# VALVEBOARD_ValveDrive3.net
KiCad netlist of a schematic drawn in Altium Designer
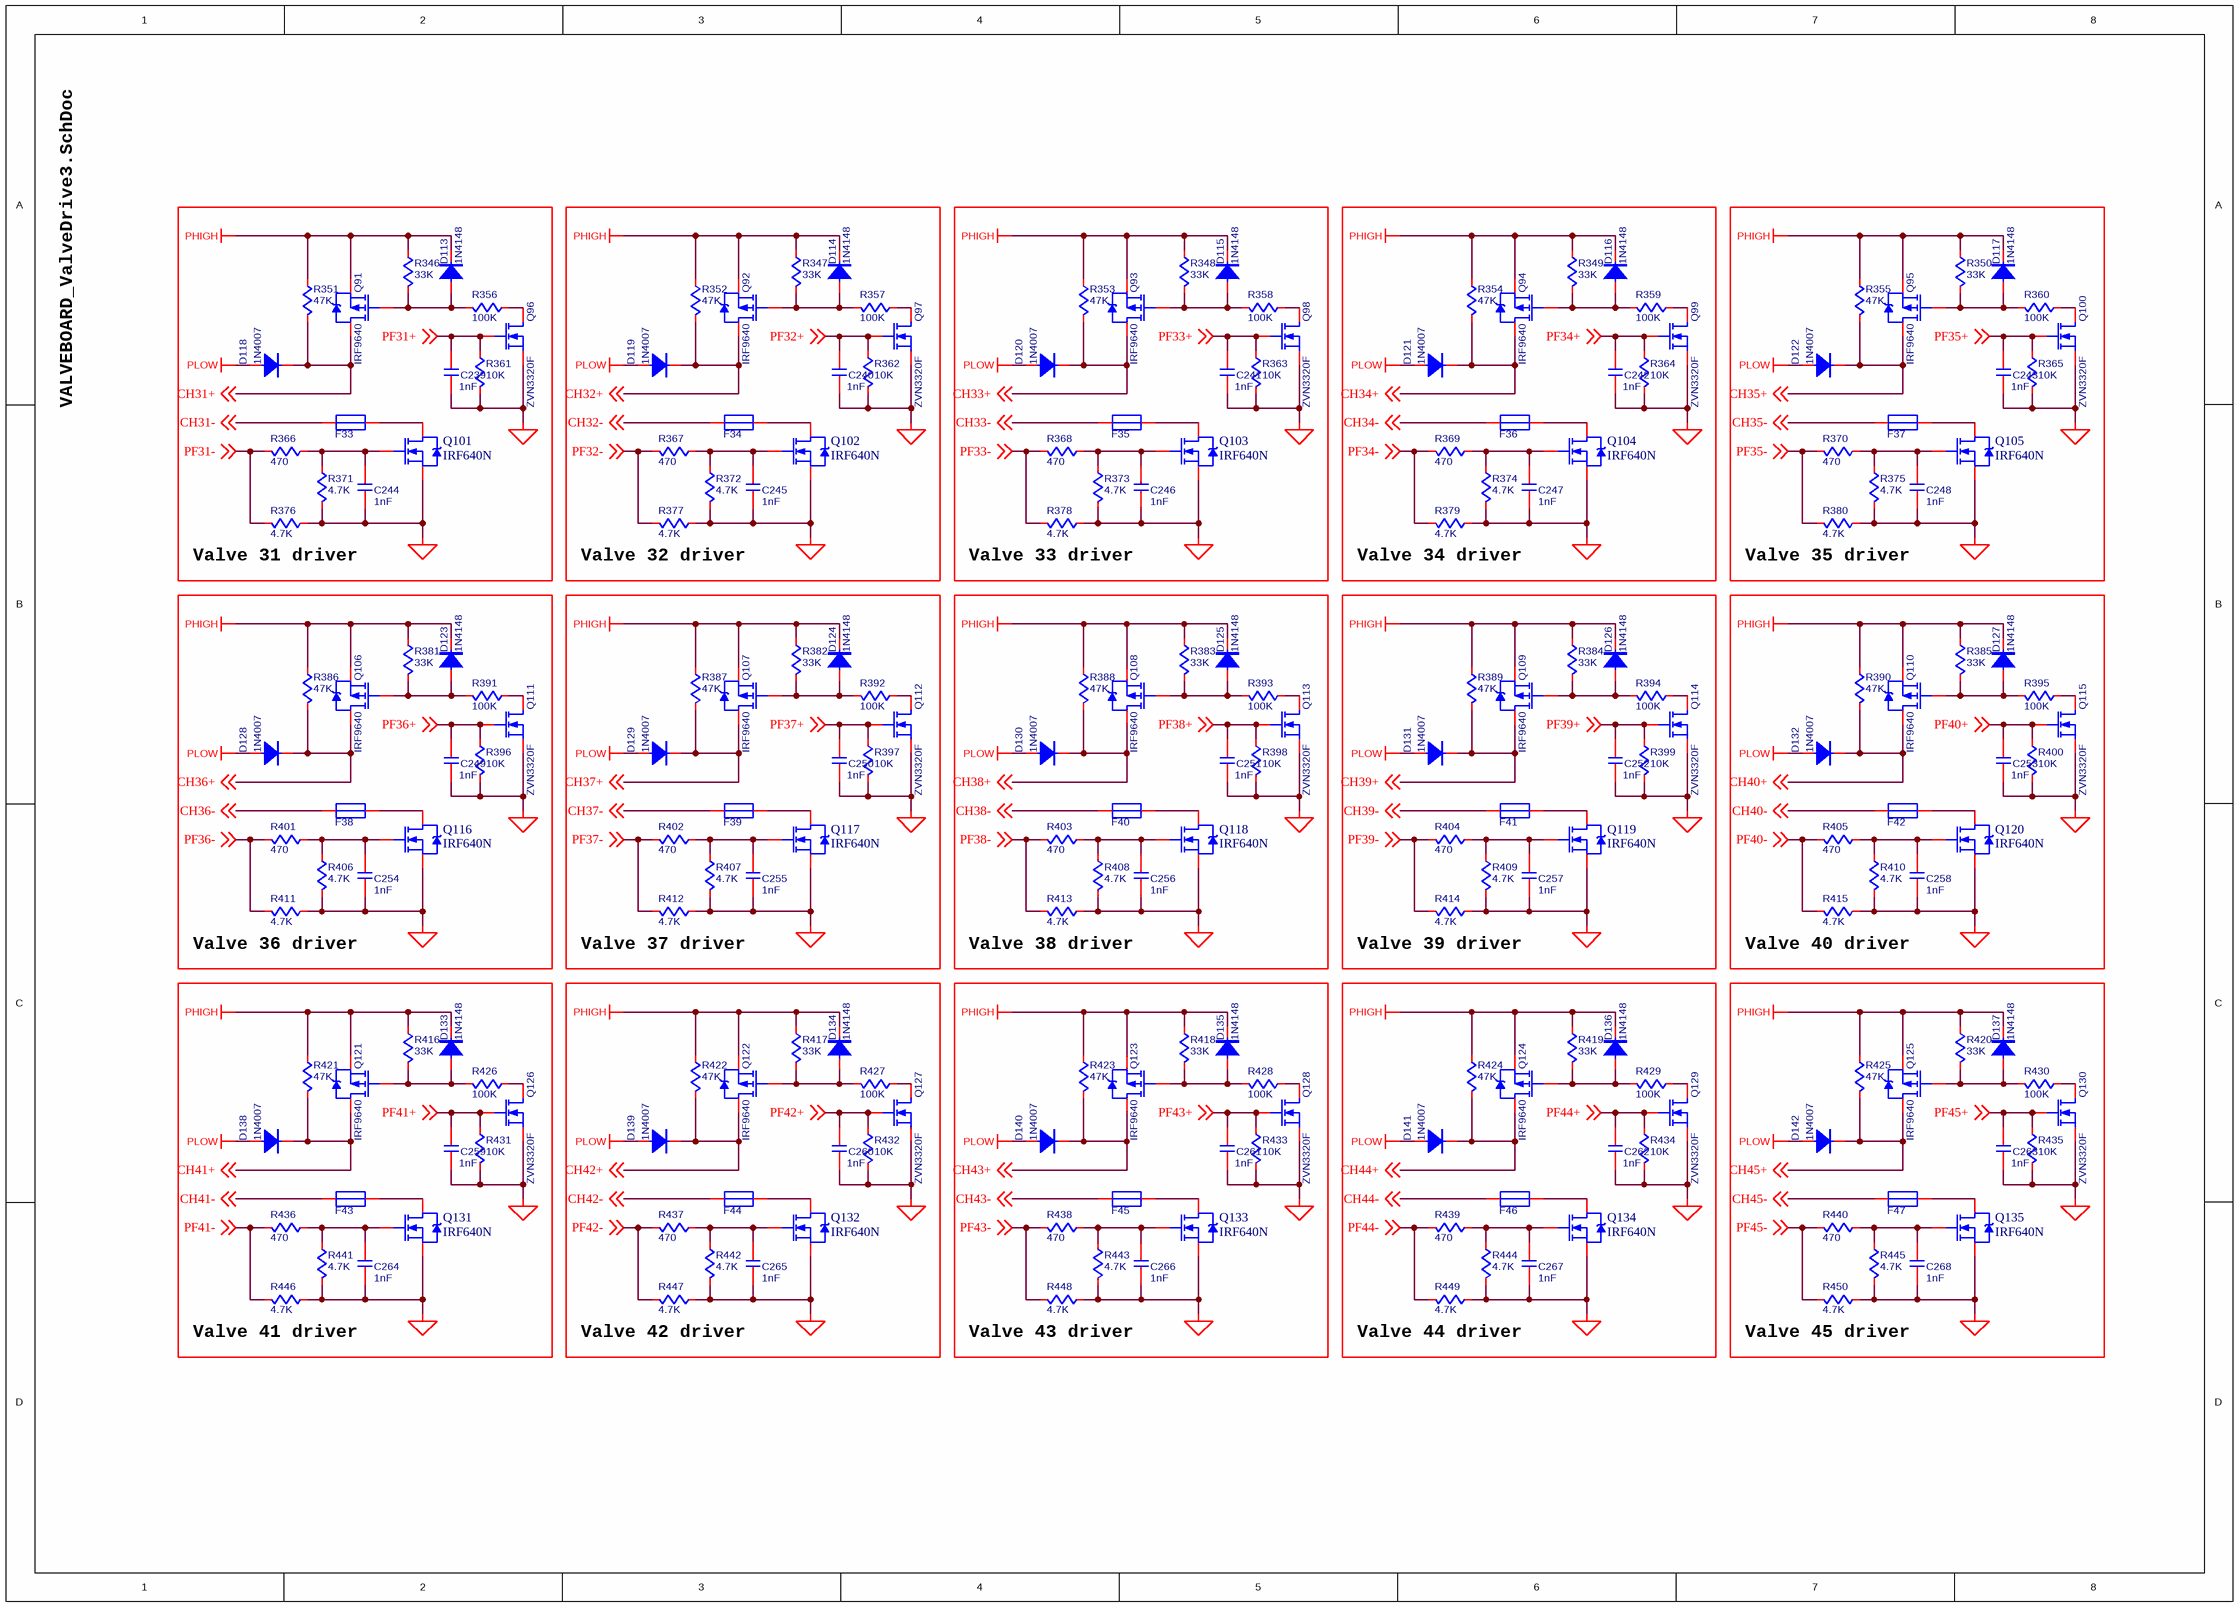
[diagram p0: VALVEBOARD_ValveDrive3.SchDoc]

(export (version "E")
  (design (tool "Eeschema 10.0.6"))
  (components
    (comp (ref "C239")
      (value "1nF")
      (footprint "zynq:C0603")
      (fields (field (name "VOLTAGE") "25V") (field (name "Comment") "C-NOMO"))
      (libsource (lib "zynq") (part "C-NOMO"))
    )
    (comp (ref "C240")
      (value "1nF")
      (footprint "zynq:C0603")
      (fields (field (name "VOLTAGE") "25V") (field (name "Comment") "C-NOMO"))
      (libsource (lib "zynq") (part "C-NOMO"))
    )
    (comp (ref "C241")
      (value "1nF")
      (footprint "zynq:C0603")
      (fields (field (name "VOLTAGE") "25V") (field (name "Comment") "C-NOMO"))
      (libsource (lib "zynq") (part "C-NOMO"))
    )
    (comp (ref "C242")
      (value "1nF")
      (footprint "zynq:C0603")
      (fields (field (name "VOLTAGE") "25V") (field (name "Comment") "C-NOMO"))
      (libsource (lib "zynq") (part "C-NOMO"))
    )
    (comp (ref "C243")
      (value "1nF")
      (footprint "zynq:C0603")
      (fields (field (name "VOLTAGE") "25V") (field (name "Comment") "C-NOMO"))
      (libsource (lib "zynq") (part "C-NOMO"))
    )
    (comp (ref "C244")
      (value "1nF")
      (footprint "zynq:C0603")
      (fields (field (name "VOLTAGE") "25V") (field (name "Comment") "C-NOMO"))
      (libsource (lib "zynq") (part "C-NOMO"))
    )
    (comp (ref "C245")
      (value "1nF")
      (footprint "zynq:C0603")
      (fields (field (name "VOLTAGE") "25V") (field (name "Comment") "C-NOMO"))
      (libsource (lib "zynq") (part "C-NOMO"))
    )
    (comp (ref "C246")
      (value "1nF")
      (footprint "zynq:C0603")
      (fields (field (name "VOLTAGE") "25V") (field (name "Comment") "C-NOMO"))
      (libsource (lib "zynq") (part "C-NOMO"))
    )
    (comp (ref "C247")
      (value "1nF")
      (footprint "zynq:C0603")
      (fields (field (name "VOLTAGE") "25V") (field (name "Comment") "C-NOMO"))
      (libsource (lib "zynq") (part "C-NOMO"))
    )
    (comp (ref "C248")
      (value "1nF")
      (footprint "zynq:C0603")
      (fields (field (name "VOLTAGE") "25V") (field (name "Comment") "C-NOMO"))
      (libsource (lib "zynq") (part "C-NOMO"))
    )
    (comp (ref "C249")
      (value "1nF")
      (footprint "zynq:C0603")
      (fields (field (name "VOLTAGE") "25V") (field (name "Comment") "C-NOMO"))
      (libsource (lib "zynq") (part "C-NOMO"))
    )
    (comp (ref "C250")
      (value "1nF")
      (footprint "zynq:C0603")
      (fields (field (name "VOLTAGE") "25V") (field (name "Comment") "C-NOMO"))
      (libsource (lib "zynq") (part "C-NOMO"))
    )
    (comp (ref "C251")
      (value "1nF")
      (footprint "zynq:C0603")
      (fields (field (name "VOLTAGE") "25V") (field (name "Comment") "C-NOMO"))
      (libsource (lib "zynq") (part "C-NOMO"))
    )
    (comp (ref "C252")
      (value "1nF")
      (footprint "zynq:C0603")
      (fields (field (name "VOLTAGE") "25V") (field (name "Comment") "C-NOMO"))
      (libsource (lib "zynq") (part "C-NOMO"))
    )
    (comp (ref "C253")
      (value "1nF")
      (footprint "zynq:C0603")
      (fields (field (name "VOLTAGE") "25V") (field (name "Comment") "C-NOMO"))
      (libsource (lib "zynq") (part "C-NOMO"))
    )
    (comp (ref "C254")
      (value "1nF")
      (footprint "zynq:C0603")
      (fields (field (name "VOLTAGE") "25V") (field (name "Comment") "C-NOMO"))
      (libsource (lib "zynq") (part "C-NOMO"))
    )
    (comp (ref "C255")
      (value "1nF")
      (footprint "zynq:C0603")
      (fields (field (name "VOLTAGE") "25V") (field (name "Comment") "C-NOMO"))
      (libsource (lib "zynq") (part "C-NOMO"))
    )
    (comp (ref "C256")
      (value "1nF")
      (footprint "zynq:C0603")
      (fields (field (name "VOLTAGE") "25V") (field (name "Comment") "C-NOMO"))
      (libsource (lib "zynq") (part "C-NOMO"))
    )
    (comp (ref "C257")
      (value "1nF")
      (footprint "zynq:C0603")
      (fields (field (name "VOLTAGE") "25V") (field (name "Comment") "C-NOMO"))
      (libsource (lib "zynq") (part "C-NOMO"))
    )
    (comp (ref "C258")
      (value "1nF")
      (footprint "zynq:C0603")
      (fields (field (name "VOLTAGE") "25V") (field (name "Comment") "C-NOMO"))
      (libsource (lib "zynq") (part "C-NOMO"))
    )
    (comp (ref "C259")
      (value "1nF")
      (footprint "zynq:C0603")
      (fields (field (name "VOLTAGE") "25V") (field (name "Comment") "C-NOMO"))
      (libsource (lib "zynq") (part "C-NOMO"))
    )
    (comp (ref "C260")
      (value "1nF")
      (footprint "zynq:C0603")
      (fields (field (name "VOLTAGE") "25V") (field (name "Comment") "C-NOMO"))
      (libsource (lib "zynq") (part "C-NOMO"))
    )
    (comp (ref "C261")
      (value "1nF")
      (footprint "zynq:C0603")
      (fields (field (name "VOLTAGE") "25V") (field (name "Comment") "C-NOMO"))
      (libsource (lib "zynq") (part "C-NOMO"))
    )
    (comp (ref "C262")
      (value "1nF")
      (footprint "zynq:C0603")
      (fields (field (name "VOLTAGE") "25V") (field (name "Comment") "C-NOMO"))
      (libsource (lib "zynq") (part "C-NOMO"))
    )
    (comp (ref "C263")
      (value "1nF")
      (footprint "zynq:C0603")
      (fields (field (name "VOLTAGE") "25V") (field (name "Comment") "C-NOMO"))
      (libsource (lib "zynq") (part "C-NOMO"))
    )
    (comp (ref "C264")
      (value "1nF")
      (footprint "zynq:C0603")
      (fields (field (name "VOLTAGE") "25V") (field (name "Comment") "C-NOMO"))
      (libsource (lib "zynq") (part "C-NOMO"))
    )
    (comp (ref "C265")
      (value "1nF")
      (footprint "zynq:C0603")
      (fields (field (name "VOLTAGE") "25V") (field (name "Comment") "C-NOMO"))
      (libsource (lib "zynq") (part "C-NOMO"))
    )
    (comp (ref "C266")
      (value "1nF")
      (footprint "zynq:C0603")
      (fields (field (name "VOLTAGE") "25V") (field (name "Comment") "C-NOMO"))
      (libsource (lib "zynq") (part "C-NOMO"))
    )
    (comp (ref "C267")
      (value "1nF")
      (footprint "zynq:C0603")
      (fields (field (name "VOLTAGE") "25V") (field (name "Comment") "C-NOMO"))
      (libsource (lib "zynq") (part "C-NOMO"))
    )
    (comp (ref "C268")
      (value "1nF")
      (footprint "zynq:C0603")
      (fields (field (name "VOLTAGE") "25V") (field (name "Comment") "C-NOMO"))
      (libsource (lib "zynq") (part "C-NOMO"))
    )
    (comp (ref "D113") (value "1N4148") (footprint "SOD-123") (libsource (lib "") (part "DIOD1_1")))
    (comp (ref "D114") (value "1N4148") (footprint "SOD-123") (libsource (lib "") (part "DIOD1_1")))
    (comp (ref "D115") (value "1N4148") (footprint "SOD-123") (libsource (lib "") (part "DIOD1_1")))
    (comp (ref "D116") (value "1N4148") (footprint "SOD-123") (libsource (lib "") (part "DIOD1_1")))
    (comp (ref "D117") (value "1N4148") (footprint "SOD-123") (libsource (lib "") (part "DIOD1_1")))
    (comp (ref "D118") (value "1N4007") (footprint "zynq:1N4148") (libsource (lib "zynq") (part "DIOD1")))
    (comp (ref "D119") (value "1N4007") (footprint "zynq:1N4148") (libsource (lib "zynq") (part "DIOD1")))
    (comp (ref "D120") (value "1N4007") (footprint "zynq:1N4148") (libsource (lib "zynq") (part "DIOD1")))
    (comp (ref "D121") (value "1N4007") (footprint "zynq:1N4148") (libsource (lib "zynq") (part "DIOD1")))
    (comp (ref "D122") (value "1N4007") (footprint "zynq:1N4148") (libsource (lib "zynq") (part "DIOD1")))
    (comp (ref "D123") (value "1N4148") (footprint "SOD-123") (libsource (lib "") (part "DIOD1_1")))
    (comp (ref "D124") (value "1N4148") (footprint "SOD-123") (libsource (lib "") (part "DIOD1_1")))
    (comp (ref "D125") (value "1N4148") (footprint "SOD-123") (libsource (lib "") (part "DIOD1_1")))
    (comp (ref "D126") (value "1N4148") (footprint "SOD-123") (libsource (lib "") (part "DIOD1_1")))
    (comp (ref "D127") (value "1N4148") (footprint "SOD-123") (libsource (lib "") (part "DIOD1_1")))
    (comp (ref "D128") (value "1N4007") (footprint "zynq:1N4148") (libsource (lib "zynq") (part "DIOD1")))
    (comp (ref "D129") (value "1N4007") (footprint "zynq:1N4148") (libsource (lib "zynq") (part "DIOD1")))
    (comp (ref "D130") (value "1N4007") (footprint "zynq:1N4148") (libsource (lib "zynq") (part "DIOD1")))
    (comp (ref "D131") (value "1N4007") (footprint "zynq:1N4148") (libsource (lib "zynq") (part "DIOD1")))
    (comp (ref "D132") (value "1N4007") (footprint "zynq:1N4148") (libsource (lib "zynq") (part "DIOD1")))
    (comp (ref "D133") (value "1N4148") (footprint "SOD-123") (libsource (lib "") (part "DIOD1_1")))
    (comp (ref "D134") (value "1N4148") (footprint "SOD-123") (libsource (lib "") (part "DIOD1_1")))
    (comp (ref "D135") (value "1N4148") (footprint "SOD-123") (libsource (lib "") (part "DIOD1_1")))
    (comp (ref "D136") (value "1N4148") (footprint "SOD-123") (libsource (lib "") (part "DIOD1_1")))
    (comp (ref "D137") (value "1N4148") (footprint "SOD-123") (libsource (lib "") (part "DIOD1_1")))
    (comp (ref "D138") (value "1N4007") (footprint "zynq:1N4148") (libsource (lib "zynq") (part "DIOD1")))
    (comp (ref "D139") (value "1N4007") (footprint "zynq:1N4148") (libsource (lib "zynq") (part "DIOD1")))
    (comp (ref "D140") (value "1N4007") (footprint "zynq:1N4148") (libsource (lib "zynq") (part "DIOD1")))
    (comp (ref "D141") (value "1N4007") (footprint "zynq:1N4148") (libsource (lib "zynq") (part "DIOD1")))
    (comp (ref "D142") (value "1N4007") (footprint "zynq:1N4148") (libsource (lib "zynq") (part "DIOD1")))
    (comp (ref "F33") (value "F50") (footprint "zynq:F-TH") (libsource (lib "zynq") (part "F50")))
    (comp (ref "F34") (value "F50") (footprint "zynq:F-TH") (libsource (lib "zynq") (part "F50")))
    (comp (ref "F35") (value "F50") (footprint "zynq:F-TH") (libsource (lib "zynq") (part "F50")))
    (comp (ref "F36") (value "F50") (footprint "zynq:F-TH") (libsource (lib "zynq") (part "F50")))
    (comp (ref "F37") (value "F50") (footprint "zynq:F-TH") (libsource (lib "zynq") (part "F50")))
    (comp (ref "F38") (value "F50") (footprint "zynq:F-TH") (libsource (lib "zynq") (part "F50")))
    (comp (ref "F39") (value "F50") (footprint "zynq:F-TH") (libsource (lib "zynq") (part "F50")))
    (comp (ref "F40") (value "F50") (footprint "zynq:F-TH") (libsource (lib "zynq") (part "F50")))
    (comp (ref "F41") (value "F50") (footprint "zynq:F-TH") (libsource (lib "zynq") (part "F50")))
    (comp (ref "F42") (value "F50") (footprint "zynq:F-TH") (libsource (lib "zynq") (part "F50")))
    (comp (ref "F43") (value "F50") (footprint "zynq:F-TH") (libsource (lib "zynq") (part "F50")))
    (comp (ref "F44") (value "F50") (footprint "zynq:F-TH") (libsource (lib "zynq") (part "F50")))
    (comp (ref "F45") (value "F50") (footprint "zynq:F-TH") (libsource (lib "zynq") (part "F50")))
    (comp (ref "F46") (value "F50") (footprint "zynq:F-TH") (libsource (lib "zynq") (part "F50")))
    (comp (ref "F47") (value "F50") (footprint "zynq:F-TH") (libsource (lib "zynq") (part "F50")))
    (comp (ref "Q91")
      (value "IRF9640")
      (footprint "TO-220AB")
      (description "P-Channel Power MOSFET")
      (fields (field (name "PUBLISHER") "Altium Limited"))
      (libsource (lib "zynq") (part "IRF9640"))
    )
    (comp (ref "Q92")
      (value "IRF9640")
      (footprint "TO-220AB")
      (description "P-Channel Power MOSFET")
      (fields (field (name "PUBLISHER") "Altium Limited"))
      (libsource (lib "zynq") (part "IRF9640"))
    )
    (comp (ref "Q93")
      (value "IRF9640")
      (footprint "TO-220AB")
      (description "P-Channel Power MOSFET")
      (fields (field (name "PUBLISHER") "Altium Limited"))
      (libsource (lib "zynq") (part "IRF9640"))
    )
    (comp (ref "Q94")
      (value "IRF9640")
      (footprint "TO-220AB")
      (description "P-Channel Power MOSFET")
      (fields (field (name "PUBLISHER") "Altium Limited"))
      (libsource (lib "zynq") (part "IRF9640"))
    )
    (comp (ref "Q95")
      (value "IRF9640")
      (footprint "TO-220AB")
      (description "P-Channel Power MOSFET")
      (fields (field (name "PUBLISHER") "Altium Limited"))
      (libsource (lib "zynq") (part "IRF9640"))
    )
    (comp (ref "Q96")
      (value "ZVN3320F")
      (footprint "zynq:ZVN3320F")
      (description "N-Channel MOSFET")
      (fields (field (name "PUBLISHER") "Altium Limited"))
      (libsource (lib "zynq") (part "ZVN3320F"))
    )
    (comp (ref "Q97")
      (value "ZVN3320F")
      (footprint "zynq:ZVN3320F")
      (description "N-Channel MOSFET")
      (fields (field (name "PUBLISHER") "Altium Limited"))
      (libsource (lib "zynq") (part "ZVN3320F"))
    )
    (comp (ref "Q98")
      (value "ZVN3320F")
      (footprint "zynq:ZVN3320F")
      (description "N-Channel MOSFET")
      (fields (field (name "PUBLISHER") "Altium Limited"))
      (libsource (lib "zynq") (part "ZVN3320F"))
    )
    (comp (ref "Q99")
      (value "ZVN3320F")
      (footprint "zynq:ZVN3320F")
      (description "N-Channel MOSFET")
      (fields (field (name "PUBLISHER") "Altium Limited"))
      (libsource (lib "zynq") (part "ZVN3320F"))
    )
    (comp (ref "Q100")
      (value "ZVN3320F")
      (footprint "zynq:ZVN3320F")
      (description "N-Channel MOSFET")
      (fields (field (name "PUBLISHER") "Altium Limited"))
      (libsource (lib "zynq") (part "ZVN3320F"))
    )
    (comp (ref "Q101")
      (value "IRF640N")
      (footprint "zynq:TO-220AB")
      (description "N-Channel Power MOSFET")
      (fields (field (name "PUBLISHER") "Altium Limited"))
      (libsource (lib "zynq") (part "IRF640N"))
    )
    (comp (ref "Q102")
      (value "IRF640N")
      (footprint "zynq:TO-220AB")
      (description "N-Channel Power MOSFET")
      (fields (field (name "PUBLISHER") "Altium Limited"))
      (libsource (lib "zynq") (part "IRF640N"))
    )
    (comp (ref "Q103")
      (value "IRF640N")
      (footprint "zynq:TO-220AB")
      (description "N-Channel Power MOSFET")
      (fields (field (name "PUBLISHER") "Altium Limited"))
      (libsource (lib "zynq") (part "IRF640N"))
    )
    (comp (ref "Q104")
      (value "IRF640N")
      (footprint "zynq:TO-220AB")
      (description "N-Channel Power MOSFET")
      (fields (field (name "PUBLISHER") "Altium Limited"))
      (libsource (lib "zynq") (part "IRF640N"))
    )
    (comp (ref "Q105")
      (value "IRF640N")
      (footprint "zynq:TO-220AB")
      (description "N-Channel Power MOSFET")
      (fields (field (name "PUBLISHER") "Altium Limited"))
      (libsource (lib "zynq") (part "IRF640N"))
    )
    (comp (ref "Q106")
      (value "IRF9640")
      (footprint "TO-220AB")
      (description "P-Channel Power MOSFET")
      (fields (field (name "PUBLISHER") "Altium Limited"))
      (libsource (lib "zynq") (part "IRF9640"))
    )
    (comp (ref "Q107")
      (value "IRF9640")
      (footprint "TO-220AB")
      (description "P-Channel Power MOSFET")
      (fields (field (name "PUBLISHER") "Altium Limited"))
      (libsource (lib "zynq") (part "IRF9640"))
    )
    (comp (ref "Q108")
      (value "IRF9640")
      (footprint "TO-220AB")
      (description "P-Channel Power MOSFET")
      (fields (field (name "PUBLISHER") "Altium Limited"))
      (libsource (lib "zynq") (part "IRF9640"))
    )
    (comp (ref "Q109")
      (value "IRF9640")
      (footprint "TO-220AB")
      (description "P-Channel Power MOSFET")
      (fields (field (name "PUBLISHER") "Altium Limited"))
      (libsource (lib "zynq") (part "IRF9640"))
    )
    (comp (ref "Q110")
      (value "IRF9640")
      (footprint "TO-220AB")
      (description "P-Channel Power MOSFET")
      (fields (field (name "PUBLISHER") "Altium Limited"))
      (libsource (lib "zynq") (part "IRF9640"))
    )
    (comp (ref "Q111")
      (value "ZVN3320F")
      (footprint "zynq:ZVN3320F")
      (description "N-Channel MOSFET")
      (fields (field (name "PUBLISHER") "Altium Limited"))
      (libsource (lib "zynq") (part "ZVN3320F"))
    )
    (comp (ref "Q112")
      (value "ZVN3320F")
      (footprint "zynq:ZVN3320F")
      (description "N-Channel MOSFET")
      (fields (field (name "PUBLISHER") "Altium Limited"))
      (libsource (lib "zynq") (part "ZVN3320F"))
    )
    (comp (ref "Q113")
      (value "ZVN3320F")
      (footprint "zynq:ZVN3320F")
      (description "N-Channel MOSFET")
      (fields (field (name "PUBLISHER") "Altium Limited"))
      (libsource (lib "zynq") (part "ZVN3320F"))
    )
    (comp (ref "Q114")
      (value "ZVN3320F")
      (footprint "zynq:ZVN3320F")
      (description "N-Channel MOSFET")
      (fields (field (name "PUBLISHER") "Altium Limited"))
      (libsource (lib "zynq") (part "ZVN3320F"))
    )
    (comp (ref "Q115")
      (value "ZVN3320F")
      (footprint "zynq:ZVN3320F")
      (description "N-Channel MOSFET")
      (fields (field (name "PUBLISHER") "Altium Limited"))
      (libsource (lib "zynq") (part "ZVN3320F"))
    )
    (comp (ref "Q116")
      (value "IRF640N")
      (footprint "zynq:TO-220AB")
      (description "N-Channel Power MOSFET")
      (fields (field (name "PUBLISHER") "Altium Limited"))
      (libsource (lib "zynq") (part "IRF640N"))
    )
    (comp (ref "Q117")
      (value "IRF640N")
      (footprint "zynq:TO-220AB")
      (description "N-Channel Power MOSFET")
      (fields (field (name "PUBLISHER") "Altium Limited"))
      (libsource (lib "zynq") (part "IRF640N"))
    )
    (comp (ref "Q118")
      (value "IRF640N")
      (footprint "zynq:TO-220AB")
      (description "N-Channel Power MOSFET")
      (fields (field (name "PUBLISHER") "Altium Limited"))
      (libsource (lib "zynq") (part "IRF640N"))
    )
    (comp (ref "Q119")
      (value "IRF640N")
      (footprint "zynq:TO-220AB")
      (description "N-Channel Power MOSFET")
      (fields (field (name "PUBLISHER") "Altium Limited"))
      (libsource (lib "zynq") (part "IRF640N"))
    )
    (comp (ref "Q120")
      (value "IRF640N")
      (footprint "zynq:TO-220AB")
      (description "N-Channel Power MOSFET")
      (fields (field (name "PUBLISHER") "Altium Limited"))
      (libsource (lib "zynq") (part "IRF640N"))
    )
    (comp (ref "Q121")
      (value "IRF9640")
      (footprint "TO-220AB")
      (description "P-Channel Power MOSFET")
      (fields (field (name "PUBLISHER") "Altium Limited"))
      (libsource (lib "zynq") (part "IRF9640"))
    )
    (comp (ref "Q122")
      (value "IRF9640")
      (footprint "TO-220AB")
      (description "P-Channel Power MOSFET")
      (fields (field (name "PUBLISHER") "Altium Limited"))
      (libsource (lib "zynq") (part "IRF9640"))
    )
    (comp (ref "Q123")
      (value "IRF9640")
      (footprint "TO-220AB")
      (description "P-Channel Power MOSFET")
      (fields (field (name "PUBLISHER") "Altium Limited"))
      (libsource (lib "zynq") (part "IRF9640"))
    )
    (comp (ref "Q124")
      (value "IRF9640")
      (footprint "TO-220AB")
      (description "P-Channel Power MOSFET")
      (fields (field (name "PUBLISHER") "Altium Limited"))
      (libsource (lib "zynq") (part "IRF9640"))
    )
    (comp (ref "Q125")
      (value "IRF9640")
      (footprint "TO-220AB")
      (description "P-Channel Power MOSFET")
      (fields (field (name "PUBLISHER") "Altium Limited"))
      (libsource (lib "zynq") (part "IRF9640"))
    )
    (comp (ref "Q126")
      (value "ZVN3320F")
      (footprint "zynq:ZVN3320F")
      (description "N-Channel MOSFET")
      (fields (field (name "PUBLISHER") "Altium Limited"))
      (libsource (lib "zynq") (part "ZVN3320F"))
    )
    (comp (ref "Q127")
      (value "ZVN3320F")
      (footprint "zynq:ZVN3320F")
      (description "N-Channel MOSFET")
      (fields (field (name "PUBLISHER") "Altium Limited"))
      (libsource (lib "zynq") (part "ZVN3320F"))
    )
    (comp (ref "Q128")
      (value "ZVN3320F")
      (footprint "zynq:ZVN3320F")
      (description "N-Channel MOSFET")
      (fields (field (name "PUBLISHER") "Altium Limited"))
      (libsource (lib "zynq") (part "ZVN3320F"))
    )
    (comp (ref "Q129")
      (value "ZVN3320F")
      (footprint "zynq:ZVN3320F")
      (description "N-Channel MOSFET")
      (fields (field (name "PUBLISHER") "Altium Limited"))
      (libsource (lib "zynq") (part "ZVN3320F"))
    )
    (comp (ref "Q130")
      (value "ZVN3320F")
      (footprint "zynq:ZVN3320F")
      (description "N-Channel MOSFET")
      (fields (field (name "PUBLISHER") "Altium Limited"))
      (libsource (lib "zynq") (part "ZVN3320F"))
    )
    (comp (ref "Q131")
      (value "IRF640N")
      (footprint "zynq:TO-220AB")
      (description "N-Channel Power MOSFET")
      (fields (field (name "PUBLISHER") "Altium Limited"))
      (libsource (lib "zynq") (part "IRF640N"))
    )
    (comp (ref "Q132")
      (value "IRF640N")
      (footprint "zynq:TO-220AB")
      (description "N-Channel Power MOSFET")
      (fields (field (name "PUBLISHER") "Altium Limited"))
      (libsource (lib "zynq") (part "IRF640N"))
    )
    (comp (ref "Q133")
      (value "IRF640N")
      (footprint "zynq:TO-220AB")
      (description "N-Channel Power MOSFET")
      (fields (field (name "PUBLISHER") "Altium Limited"))
      (libsource (lib "zynq") (part "IRF640N"))
    )
    (comp (ref "Q134")
      (value "IRF640N")
      (footprint "zynq:TO-220AB")
      (description "N-Channel Power MOSFET")
      (fields (field (name "PUBLISHER") "Altium Limited"))
      (libsource (lib "zynq") (part "IRF640N"))
    )
    (comp (ref "Q135")
      (value "IRF640N")
      (footprint "zynq:TO-220AB")
      (description "N-Channel Power MOSFET")
      (fields (field (name "PUBLISHER") "Altium Limited"))
      (libsource (lib "zynq") (part "IRF640N"))
    )
    (comp (ref "R346")
      (value "33K")
      (footprint "zynq:R0603")
      (fields (field (name "Comment") "R"))
      (libsource (lib "zynq") (part "R"))
    )
    (comp (ref "R347")
      (value "33K")
      (footprint "zynq:R0603")
      (fields (field (name "Comment") "R"))
      (libsource (lib "zynq") (part "R"))
    )
    (comp (ref "R348")
      (value "33K")
      (footprint "zynq:R0603")
      (fields (field (name "Comment") "R"))
      (libsource (lib "zynq") (part "R"))
    )
    (comp (ref "R349")
      (value "33K")
      (footprint "zynq:R0603")
      (fields (field (name "Comment") "R"))
      (libsource (lib "zynq") (part "R"))
    )
    (comp (ref "R350")
      (value "33K")
      (footprint "zynq:R0603")
      (fields (field (name "Comment") "R"))
      (libsource (lib "zynq") (part "R"))
    )
    (comp (ref "R351")
      (value "47K")
      (footprint "R2512")
      (fields (field (name "Comment") "R"))
      (libsource (lib "zynq") (part "R"))
    )
    (comp (ref "R352")
      (value "47K")
      (footprint "R2512")
      (fields (field (name "Comment") "R"))
      (libsource (lib "zynq") (part "R"))
    )
    (comp (ref "R353")
      (value "47K")
      (footprint "R2512")
      (fields (field (name "Comment") "R"))
      (libsource (lib "zynq") (part "R"))
    )
    (comp (ref "R354")
      (value "47K")
      (footprint "R2512")
      (fields (field (name "Comment") "R"))
      (libsource (lib "zynq") (part "R"))
    )
    (comp (ref "R355")
      (value "47K")
      (footprint "R2512")
      (fields (field (name "Comment") "R"))
      (libsource (lib "zynq") (part "R"))
    )
    (comp (ref "R356")
      (value "100K")
      (footprint "zynq:R0603")
      (fields (field (name "Comment") "R"))
      (libsource (lib "zynq") (part "R"))
    )
    (comp (ref "R357")
      (value "100K")
      (footprint "zynq:R0603")
      (fields (field (name "Comment") "R"))
      (libsource (lib "zynq") (part "R"))
    )
    (comp (ref "R358")
      (value "100K")
      (footprint "zynq:R0603")
      (fields (field (name "Comment") "R"))
      (libsource (lib "zynq") (part "R"))
    )
    (comp (ref "R359")
      (value "100K")
      (footprint "zynq:R0603")
      (fields (field (name "Comment") "R"))
      (libsource (lib "zynq") (part "R"))
    )
    (comp (ref "R360")
      (value "100K")
      (footprint "zynq:R0603")
      (fields (field (name "Comment") "R"))
      (libsource (lib "zynq") (part "R"))
    )
    (comp (ref "R361")
      (value "10K")
      (footprint "zynq:R0603")
      (fields (field (name "Comment") "R"))
      (libsource (lib "zynq") (part "R"))
    )
    (comp (ref "R362")
      (value "10K")
      (footprint "zynq:R0603")
      (fields (field (name "Comment") "R"))
      (libsource (lib "zynq") (part "R"))
    )
    (comp (ref "R363")
      (value "10K")
      (footprint "zynq:R0603")
      (fields (field (name "Comment") "R"))
      (libsource (lib "zynq") (part "R"))
    )
    (comp (ref "R364")
      (value "10K")
      (footprint "zynq:R0603")
      (fields (field (name "Comment") "R"))
      (libsource (lib "zynq") (part "R"))
    )
    (comp (ref "R365")
      (value "10K")
      (footprint "zynq:R0603")
      (fields (field (name "Comment") "R"))
      (libsource (lib "zynq") (part "R"))
    )
    (comp (ref "R366")
      (value "470")
      (footprint "zynq:R0402")
      (fields (field (name "Comment") "R"))
      (libsource (lib "zynq") (part "R"))
    )
    (comp (ref "R367")
      (value "470")
      (footprint "zynq:R0402")
      (fields (field (name "Comment") "R"))
      (libsource (lib "zynq") (part "R"))
    )
    (comp (ref "R368")
      (value "470")
      (footprint "zynq:R0402")
      (fields (field (name "Comment") "R"))
      (libsource (lib "zynq") (part "R"))
    )
    (comp (ref "R369")
      (value "470")
      (footprint "zynq:R0402")
      (fields (field (name "Comment") "R"))
      (libsource (lib "zynq") (part "R"))
    )
    (comp (ref "R370")
      (value "470")
      (footprint "zynq:R0402")
      (fields (field (name "Comment") "R"))
      (libsource (lib "zynq") (part "R"))
    )
    (comp (ref "R371")
      (value "4.7K")
      (footprint "zynq:R0402")
      (fields (field (name "Comment") "R"))
      (libsource (lib "zynq") (part "R"))
    )
    (comp (ref "R372")
      (value "4.7K")
      (footprint "zynq:R0402")
      (fields (field (name "Comment") "R"))
      (libsource (lib "zynq") (part "R"))
    )
    (comp (ref "R373")
      (value "4.7K")
      (footprint "zynq:R0402")
      (fields (field (name "Comment") "R"))
      (libsource (lib "zynq") (part "R"))
    )
    (comp (ref "R374")
      (value "4.7K")
      (footprint "zynq:R0402")
      (fields (field (name "Comment") "R"))
      (libsource (lib "zynq") (part "R"))
    )
    (comp (ref "R375")
      (value "4.7K")
      (footprint "zynq:R0402")
      (fields (field (name "Comment") "R"))
      (libsource (lib "zynq") (part "R"))
    )
    (comp (ref "R376")
      (value "4.7K")
      (footprint "zynq:R0402")
      (fields (field (name "Comment") "R"))
      (libsource (lib "zynq") (part "R"))
    )
    (comp (ref "R377")
      (value "4.7K")
      (footprint "zynq:R0402")
      (fields (field (name "Comment") "R"))
      (libsource (lib "zynq") (part "R"))
    )
    (comp (ref "R378")
      (value "4.7K")
      (footprint "zynq:R0402")
      (fields (field (name "Comment") "R"))
      (libsource (lib "zynq") (part "R"))
    )
    (comp (ref "R379")
      (value "4.7K")
      (footprint "zynq:R0402")
      (fields (field (name "Comment") "R"))
      (libsource (lib "zynq") (part "R"))
    )
    (comp (ref "R380")
      (value "4.7K")
      (footprint "zynq:R0402")
      (fields (field (name "Comment") "R"))
      (libsource (lib "zynq") (part "R"))
    )
    (comp (ref "R381")
      (value "33K")
      (footprint "zynq:R0603")
      (fields (field (name "Comment") "R"))
      (libsource (lib "zynq") (part "R"))
    )
    (comp (ref "R382")
      (value "33K")
      (footprint "zynq:R0603")
      (fields (field (name "Comment") "R"))
      (libsource (lib "zynq") (part "R"))
    )
    (comp (ref "R383")
      (value "33K")
      (footprint "zynq:R0603")
      (fields (field (name "Comment") "R"))
      (libsource (lib "zynq") (part "R"))
    )
    (comp (ref "R384")
      (value "33K")
      (footprint "zynq:R0603")
      (fields (field (name "Comment") "R"))
      (libsource (lib "zynq") (part "R"))
    )
    (comp (ref "R385")
      (value "33K")
      (footprint "zynq:R0603")
      (fields (field (name "Comment") "R"))
      (libsource (lib "zynq") (part "R"))
    )
    (comp (ref "R386")
      (value "47K")
      (footprint "R2512")
      (fields (field (name "Comment") "R"))
      (libsource (lib "zynq") (part "R"))
    )
    (comp (ref "R387")
      (value "47K")
      (footprint "R2512")
      (fields (field (name "Comment") "R"))
      (libsource (lib "zynq") (part "R"))
    )
    (comp (ref "R388")
      (value "47K")
      (footprint "R2512")
      (fields (field (name "Comment") "R"))
      (libsource (lib "zynq") (part "R"))
    )
    (comp (ref "R389")
      (value "47K")
      (footprint "R2512")
      (fields (field (name "Comment") "R"))
      (libsource (lib "zynq") (part "R"))
    )
    (comp (ref "R390")
      (value "47K")
      (footprint "R2512")
      (fields (field (name "Comment") "R"))
      (libsource (lib "zynq") (part "R"))
    )
    (comp (ref "R391")
      (value "100K")
      (footprint "zynq:R0603")
      (fields (field (name "Comment") "R"))
      (libsource (lib "zynq") (part "R"))
    )
    (comp (ref "R392")
      (value "100K")
      (footprint "zynq:R0603")
      (fields (field (name "Comment") "R"))
      (libsource (lib "zynq") (part "R"))
    )
    (comp (ref "R393")
      (value "100K")
      (footprint "zynq:R0603")
      (fields (field (name "Comment") "R"))
      (libsource (lib "zynq") (part "R"))
    )
    (comp (ref "R394")
      (value "100K")
      (footprint "zynq:R0603")
      (fields (field (name "Comment") "R"))
      (libsource (lib "zynq") (part "R"))
    )
    (comp (ref "R395")
      (value "100K")
      (footprint "zynq:R0603")
      (fields (field (name "Comment") "R"))
      (libsource (lib "zynq") (part "R"))
    )
    (comp (ref "R396")
      (value "10K")
      (footprint "zynq:R0603")
      (fields (field (name "Comment") "R"))
      (libsource (lib "zynq") (part "R"))
    )
    (comp (ref "R397")
      (value "10K")
      (footprint "zynq:R0603")
      (fields (field (name "Comment") "R"))
      (libsource (lib "zynq") (part "R"))
    )
    (comp (ref "R398")
      (value "10K")
      (footprint "zynq:R0603")
      (fields (field (name "Comment") "R"))
      (libsource (lib "zynq") (part "R"))
    )
    (comp (ref "R399")
      (value "10K")
      (footprint "zynq:R0603")
      (fields (field (name "Comment") "R"))
      (libsource (lib "zynq") (part "R"))
    )
    (comp (ref "R400")
      (value "10K")
      (footprint "zynq:R0603")
      (fields (field (name "Comment") "R"))
      (libsource (lib "zynq") (part "R"))
    )
    (comp (ref "R401")
      (value "470")
      (footprint "zynq:R0402")
      (fields (field (name "Comment") "R"))
      (libsource (lib "zynq") (part "R"))
    )
    (comp (ref "R402")
      (value "470")
      (footprint "zynq:R0402")
      (fields (field (name "Comment") "R"))
      (libsource (lib "zynq") (part "R"))
    )
    (comp (ref "R403")
      (value "470")
      (footprint "zynq:R0402")
      (fields (field (name "Comment") "R"))
      (libsource (lib "zynq") (part "R"))
    )
    (comp (ref "R404")
      (value "470")
      (footprint "zynq:R0402")
      (fields (field (name "Comment") "R"))
      (libsource (lib "zynq") (part "R"))
    )
    (comp (ref "R405")
      (value "470")
      (footprint "zynq:R0402")
      (fields (field (name "Comment") "R"))
      (libsource (lib "zynq") (part "R"))
    )
    (comp (ref "R406")
      (value "4.7K")
      (footprint "zynq:R0402")
      (fields (field (name "Comment") "R"))
      (libsource (lib "zynq") (part "R"))
    )
    (comp (ref "R407")
      (value "4.7K")
      (footprint "zynq:R0402")
      (fields (field (name "Comment") "R"))
      (libsource (lib "zynq") (part "R"))
    )
    (comp (ref "R408")
      (value "4.7K")
      (footprint "zynq:R0402")
      (fields (field (name "Comment") "R"))
      (libsource (lib "zynq") (part "R"))
    )
    (comp (ref "R409")
      (value "4.7K")
      (footprint "zynq:R0402")
      (fields (field (name "Comment") "R"))
      (libsource (lib "zynq") (part "R"))
    )
    (comp (ref "R410")
      (value "4.7K")
      (footprint "zynq:R0402")
      (fields (field (name "Comment") "R"))
      (libsource (lib "zynq") (part "R"))
    )
    (comp (ref "R411")
      (value "4.7K")
      (footprint "zynq:R0402")
      (fields (field (name "Comment") "R"))
      (libsource (lib "zynq") (part "R"))
    )
    (comp (ref "R412")
      (value "4.7K")
      (footprint "zynq:R0402")
      (fields (field (name "Comment") "R"))
      (libsource (lib "zynq") (part "R"))
    )
    (comp (ref "R413")
      (value "4.7K")
      (footprint "zynq:R0402")
      (fields (field (name "Comment") "R"))
      (libsource (lib "zynq") (part "R"))
    )
    (comp (ref "R414")
      (value "4.7K")
      (footprint "zynq:R0402")
      (fields (field (name "Comment") "R"))
      (libsource (lib "zynq") (part "R"))
    )
    (comp (ref "R415")
      (value "4.7K")
      (footprint "zynq:R0402")
      (fields (field (name "Comment") "R"))
      (libsource (lib "zynq") (part "R"))
    )
    (comp (ref "R416")
      (value "33K")
      (footprint "zynq:R0603")
      (fields (field (name "Comment") "R"))
      (libsource (lib "zynq") (part "R"))
    )
    (comp (ref "R417")
      (value "33K")
      (footprint "zynq:R0603")
      (fields (field (name "Comment") "R"))
      (libsource (lib "zynq") (part "R"))
    )
    (comp (ref "R418")
      (value "33K")
      (footprint "zynq:R0603")
      (fields (field (name "Comment") "R"))
      (libsource (lib "zynq") (part "R"))
    )
    (comp (ref "R419")
      (value "33K")
      (footprint "zynq:R0603")
      (fields (field (name "Comment") "R"))
      (libsource (lib "zynq") (part "R"))
    )
    (comp (ref "R420")
      (value "33K")
      (footprint "zynq:R0603")
      (fields (field (name "Comment") "R"))
      (libsource (lib "zynq") (part "R"))
    )
    (comp (ref "R421")
      (value "47K")
      (footprint "R2512")
      (fields (field (name "Comment") "R"))
      (libsource (lib "zynq") (part "R"))
    )
    (comp (ref "R422")
      (value "47K")
      (footprint "R2512")
      (fields (field (name "Comment") "R"))
      (libsource (lib "zynq") (part "R"))
    )
    (comp (ref "R423")
      (value "47K")
      (footprint "R2512")
      (fields (field (name "Comment") "R"))
      (libsource (lib "zynq") (part "R"))
    )
    (comp (ref "R424")
      (value "47K")
      (footprint "R2512")
      (fields (field (name "Comment") "R"))
      (libsource (lib "zynq") (part "R"))
    )
    (comp (ref "R425")
      (value "47K")
      (footprint "R2512")
      (fields (field (name "Comment") "R"))
      (libsource (lib "zynq") (part "R"))
    )
    (comp (ref "R426")
      (value "100K")
      (footprint "zynq:R0603")
      (fields (field (name "Comment") "R"))
      (libsource (lib "zynq") (part "R"))
    )
    (comp (ref "R427")
      (value "100K")
      (footprint "zynq:R0603")
      (fields (field (name "Comment") "R"))
      (libsource (lib "zynq") (part "R"))
    )
    (comp (ref "R428")
      (value "100K")
      (footprint "zynq:R0603")
      (fields (field (name "Comment") "R"))
      (libsource (lib "zynq") (part "R"))
    )
    (comp (ref "R429")
      (value "100K")
      (footprint "zynq:R0603")
      (fields (field (name "Comment") "R"))
      (libsource (lib "zynq") (part "R"))
    )
    (comp (ref "R430")
      (value "100K")
      (footprint "zynq:R0603")
      (fields (field (name "Comment") "R"))
      (libsource (lib "zynq") (part "R"))
    )
    (comp (ref "R431")
      (value "10K")
      (footprint "zynq:R0603")
      (fields (field (name "Comment") "R"))
      (libsource (lib "zynq") (part "R"))
    )
    (comp (ref "R432")
      (value "10K")
      (footprint "zynq:R0603")
      (fields (field (name "Comment") "R"))
      (libsource (lib "zynq") (part "R"))
    )
    (comp (ref "R433")
      (value "10K")
      (footprint "zynq:R0603")
      (fields (field (name "Comment") "R"))
      (libsource (lib "zynq") (part "R"))
    )
    (comp (ref "R434")
      (value "10K")
      (footprint "zynq:R0603")
      (fields (field (name "Comment") "R"))
      (libsource (lib "zynq") (part "R"))
    )
    (comp (ref "R435")
      (value "10K")
      (footprint "zynq:R0603")
      (fields (field (name "Comment") "R"))
      (libsource (lib "zynq") (part "R"))
    )
    (comp (ref "R436")
      (value "470")
      (footprint "zynq:R0402")
      (fields (field (name "Comment") "R"))
      (libsource (lib "zynq") (part "R"))
    )
    (comp (ref "R437")
      (value "470")
      (footprint "zynq:R0402")
      (fields (field (name "Comment") "R"))
      (libsource (lib "zynq") (part "R"))
    )
    (comp (ref "R438")
      (value "470")
      (footprint "zynq:R0402")
      (fields (field (name "Comment") "R"))
      (libsource (lib "zynq") (part "R"))
    )
    (comp (ref "R439")
      (value "470")
      (footprint "zynq:R0402")
      (fields (field (name "Comment") "R"))
      (libsource (lib "zynq") (part "R"))
    )
    (comp (ref "R440")
      (value "470")
      (footprint "zynq:R0402")
      (fields (field (name "Comment") "R"))
      (libsource (lib "zynq") (part "R"))
    )
    (comp (ref "R441")
      (value "4.7K")
      (footprint "zynq:R0402")
      (fields (field (name "Comment") "R"))
      (libsource (lib "zynq") (part "R"))
    )
    (comp (ref "R442")
      (value "4.7K")
      (footprint "zynq:R0402")
      (fields (field (name "Comment") "R"))
      (libsource (lib "zynq") (part "R"))
    )
    (comp (ref "R443")
      (value "4.7K")
      (footprint "zynq:R0402")
      (fields (field (name "Comment") "R"))
      (libsource (lib "zynq") (part "R"))
    )
    (comp (ref "R444")
      (value "4.7K")
      (footprint "zynq:R0402")
      (fields (field (name "Comment") "R"))
      (libsource (lib "zynq") (part "R"))
    )
    (comp (ref "R445")
      (value "4.7K")
      (footprint "zynq:R0402")
      (fields (field (name "Comment") "R"))
      (libsource (lib "zynq") (part "R"))
    )
    (comp (ref "R446")
      (value "4.7K")
      (footprint "zynq:R0402")
      (fields (field (name "Comment") "R"))
      (libsource (lib "zynq") (part "R"))
    )
    (comp (ref "R447")
      (value "4.7K")
      (footprint "zynq:R0402")
      (fields (field (name "Comment") "R"))
      (libsource (lib "zynq") (part "R"))
    )
    (comp (ref "R448")
      (value "4.7K")
      (footprint "zynq:R0402")
      (fields (field (name "Comment") "R"))
      (libsource (lib "zynq") (part "R"))
    )
    (comp (ref "R449")
      (value "4.7K")
      (footprint "zynq:R0402")
      (fields (field (name "Comment") "R"))
      (libsource (lib "zynq") (part "R"))
    )
    (comp (ref "R450")
      (value "4.7K")
      (footprint "zynq:R0402")
      (fields (field (name "Comment") "R"))
      (libsource (lib "zynq") (part "R"))
    )
  )
  (nets
    (net (code "1") (name "CH31+") (class "Default")
      (node (ref "D118") (pin "1") (pinfunction "1_1") (pintype "passive"))
      (node (ref "Q91") (pin "2") (pinfunction "D_2") (pintype "passive"))
      (node (ref "R351") (pin "1") (pinfunction "1_1") (pintype "passive"))
    )
    (net (code "2") (name "CH31-") (class "Default") (node (ref "F33") (pin "1") (pintype "passive")))
    (net (code "3") (name "CH32+") (class "Default")
      (node (ref "D119") (pin "1") (pinfunction "1_1") (pintype "passive"))
      (node (ref "Q92") (pin "2") (pinfunction "D_2") (pintype "passive"))
      (node (ref "R352") (pin "1") (pinfunction "1_1") (pintype "passive"))
    )
    (net (code "4") (name "CH32-") (class "Default") (node (ref "F34") (pin "1") (pintype "passive")))
    (net (code "5") (name "CH33+") (class "Default")
      (node (ref "D120") (pin "1") (pinfunction "1_1") (pintype "passive"))
      (node (ref "Q93") (pin "2") (pinfunction "D_2") (pintype "passive"))
      (node (ref "R353") (pin "1") (pinfunction "1_1") (pintype "passive"))
    )
    (net (code "6") (name "CH33-") (class "Default") (node (ref "F35") (pin "1") (pintype "passive")))
    (net (code "7") (name "CH34+") (class "Default")
      (node (ref "D121") (pin "1") (pinfunction "1_1") (pintype "passive"))
      (node (ref "Q94") (pin "2") (pinfunction "D_2") (pintype "passive"))
      (node (ref "R354") (pin "1") (pinfunction "1_1") (pintype "passive"))
    )
    (net (code "8") (name "CH34-") (class "Default") (node (ref "F36") (pin "1") (pintype "passive")))
    (net (code "9") (name "CH35+") (class "Default")
      (node (ref "D122") (pin "1") (pinfunction "1_1") (pintype "passive"))
      (node (ref "Q95") (pin "2") (pinfunction "D_2") (pintype "passive"))
      (node (ref "R355") (pin "1") (pinfunction "1_1") (pintype "passive"))
    )
    (net (code "10") (name "CH35-") (class "Default") (node (ref "F37") (pin "1") (pintype "passive")))
    (net (code "11") (name "CH36+") (class "Default")
      (node (ref "D128") (pin "1") (pinfunction "1_1") (pintype "passive"))
      (node (ref "Q106") (pin "2") (pinfunction "D_2") (pintype "passive"))
      (node (ref "R386") (pin "1") (pinfunction "1_1") (pintype "passive"))
    )
    (net (code "12") (name "CH36-") (class "Default") (node (ref "F38") (pin "1") (pintype "passive")))
    (net (code "13") (name "CH37+") (class "Default")
      (node (ref "D129") (pin "1") (pinfunction "1_1") (pintype "passive"))
      (node (ref "Q107") (pin "2") (pinfunction "D_2") (pintype "passive"))
      (node (ref "R387") (pin "1") (pinfunction "1_1") (pintype "passive"))
    )
    (net (code "14") (name "CH37-") (class "Default") (node (ref "F39") (pin "1") (pintype "passive")))
    (net (code "15") (name "CH38+") (class "Default")
      (node (ref "D130") (pin "1") (pinfunction "1_1") (pintype "passive"))
      (node (ref "Q108") (pin "2") (pinfunction "D_2") (pintype "passive"))
      (node (ref "R388") (pin "1") (pinfunction "1_1") (pintype "passive"))
    )
    (net (code "16") (name "CH38-") (class "Default") (node (ref "F40") (pin "1") (pintype "passive")))
    (net (code "17") (name "CH39+") (class "Default")
      (node (ref "D131") (pin "1") (pinfunction "1_1") (pintype "passive"))
      (node (ref "Q109") (pin "2") (pinfunction "D_2") (pintype "passive"))
      (node (ref "R389") (pin "1") (pinfunction "1_1") (pintype "passive"))
    )
    (net (code "18") (name "CH39-") (class "Default") (node (ref "F41") (pin "1") (pintype "passive")))
    (net (code "19") (name "CH40+") (class "Default")
      (node (ref "D132") (pin "1") (pinfunction "1_1") (pintype "passive"))
      (node (ref "Q110") (pin "2") (pinfunction "D_2") (pintype "passive"))
      (node (ref "R390") (pin "1") (pinfunction "1_1") (pintype "passive"))
    )
    (net (code "20") (name "CH40-") (class "Default") (node (ref "F42") (pin "1") (pintype "passive")))
    (net (code "21") (name "CH41+") (class "Default")
      (node (ref "D138") (pin "1") (pinfunction "1_1") (pintype "passive"))
      (node (ref "Q121") (pin "2") (pinfunction "D_2") (pintype "passive"))
      (node (ref "R421") (pin "1") (pinfunction "1_1") (pintype "passive"))
    )
    (net (code "22") (name "CH41-") (class "Default") (node (ref "F43") (pin "1") (pintype "passive")))
    (net (code "23") (name "CH42+") (class "Default")
      (node (ref "D139") (pin "1") (pinfunction "1_1") (pintype "passive"))
      (node (ref "Q122") (pin "2") (pinfunction "D_2") (pintype "passive"))
      (node (ref "R422") (pin "1") (pinfunction "1_1") (pintype "passive"))
    )
    (net (code "24") (name "CH42-") (class "Default") (node (ref "F44") (pin "1") (pintype "passive")))
    (net (code "25") (name "CH43+") (class "Default")
      (node (ref "D140") (pin "1") (pinfunction "1_1") (pintype "passive"))
      (node (ref "Q123") (pin "2") (pinfunction "D_2") (pintype "passive"))
      (node (ref "R423") (pin "1") (pinfunction "1_1") (pintype "passive"))
    )
    (net (code "26") (name "CH43-") (class "Default") (node (ref "F45") (pin "1") (pintype "passive")))
    (net (code "27") (name "CH44+") (class "Default")
      (node (ref "D141") (pin "1") (pinfunction "1_1") (pintype "passive"))
      (node (ref "Q124") (pin "2") (pinfunction "D_2") (pintype "passive"))
      (node (ref "R424") (pin "1") (pinfunction "1_1") (pintype "passive"))
    )
    (net (code "28") (name "CH44-") (class "Default") (node (ref "F46") (pin "1") (pintype "passive")))
    (net (code "29") (name "CH45+") (class "Default")
      (node (ref "D142") (pin "1") (pinfunction "1_1") (pintype "passive"))
      (node (ref "Q125") (pin "2") (pinfunction "D_2") (pintype "passive"))
      (node (ref "R425") (pin "1") (pinfunction "1_1") (pintype "passive"))
    )
    (net (code "30") (name "CH45-") (class "Default") (node (ref "F47") (pin "1") (pintype "passive")))
    (net (code "31") (name "Net-(Q91-G)") (class "Default")
      (node (ref "D113") (pin "2") (pinfunction "2_2") (pintype "passive"))
      (node (ref "Q91") (pin "1") (pinfunction "G_1") (pintype "passive"))
      (node (ref "R346") (pin "1") (pinfunction "1_1") (pintype "passive"))
      (node (ref "R356") (pin "1") (pinfunction "1_1") (pintype "passive"))
    )
    (net (code "32") (name "Net-(Q92-G)") (class "Default")
      (node (ref "D114") (pin "2") (pinfunction "2_2") (pintype "passive"))
      (node (ref "Q92") (pin "1") (pinfunction "G_1") (pintype "passive"))
      (node (ref "R347") (pin "1") (pinfunction "1_1") (pintype "passive"))
      (node (ref "R357") (pin "1") (pinfunction "1_1") (pintype "passive"))
    )
    (net (code "33") (name "Net-(Q93-G)") (class "Default")
      (node (ref "D115") (pin "2") (pinfunction "2_2") (pintype "passive"))
      (node (ref "Q93") (pin "1") (pinfunction "G_1") (pintype "passive"))
      (node (ref "R348") (pin "1") (pinfunction "1_1") (pintype "passive"))
      (node (ref "R358") (pin "1") (pinfunction "1_1") (pintype "passive"))
    )
    (net (code "34") (name "Net-(Q94-G)") (class "Default")
      (node (ref "D116") (pin "2") (pinfunction "2_2") (pintype "passive"))
      (node (ref "Q94") (pin "1") (pinfunction "G_1") (pintype "passive"))
      (node (ref "R349") (pin "1") (pinfunction "1_1") (pintype "passive"))
      (node (ref "R359") (pin "1") (pinfunction "1_1") (pintype "passive"))
    )
    (net (code "35") (name "Net-(Q95-G)") (class "Default")
      (node (ref "D117") (pin "2") (pinfunction "2_2") (pintype "passive"))
      (node (ref "Q95") (pin "1") (pinfunction "G_1") (pintype "passive"))
      (node (ref "R350") (pin "1") (pinfunction "1_1") (pintype "passive"))
      (node (ref "R360") (pin "1") (pinfunction "1_1") (pintype "passive"))
    )
    (net (code "36") (name "Net-(Q96-D)") (class "Default")
      (node (ref "Q96") (pin "1") (pinfunction "D_1") (pintype "passive"))
      (node (ref "R356") (pin "2") (pinfunction "2_2") (pintype "passive"))
    )
    (net (code "37") (name "Net-(Q97-D)") (class "Default")
      (node (ref "Q97") (pin "1") (pinfunction "D_1") (pintype "passive"))
      (node (ref "R357") (pin "2") (pinfunction "2_2") (pintype "passive"))
    )
    (net (code "38") (name "Net-(Q98-D)") (class "Default")
      (node (ref "Q98") (pin "1") (pinfunction "D_1") (pintype "passive"))
      (node (ref "R358") (pin "2") (pinfunction "2_2") (pintype "passive"))
    )
    (net (code "39") (name "Net-(Q99-D)") (class "Default")
      (node (ref "Q99") (pin "1") (pinfunction "D_1") (pintype "passive"))
      (node (ref "R359") (pin "2") (pinfunction "2_2") (pintype "passive"))
    )
    (net (code "40") (name "Net-(Q100-D)") (class "Default")
      (node (ref "Q100") (pin "1") (pinfunction "D_1") (pintype "passive"))
      (node (ref "R360") (pin "2") (pinfunction "2_2") (pintype "passive"))
    )
    (net (code "41") (name "Net-(Q101-D)") (class "Default")
      (node (ref "F33") (pin "2") (pintype "passive"))
      (node (ref "Q101") (pin "2") (pinfunction "D_2") (pintype "passive"))
    )
    (net (code "42") (name "Net-(Q101-G)") (class "Default")
      (node (ref "C244") (pin "2") (pinfunction "2_2") (pintype "passive"))
      (node (ref "Q101") (pin "1") (pinfunction "G_1") (pintype "passive"))
      (node (ref "R366") (pin "2") (pinfunction "2_2") (pintype "passive"))
      (node (ref "R371") (pin "2") (pinfunction "2_2") (pintype "passive"))
    )
    (net (code "43") (name "Net-(Q102-D)") (class "Default")
      (node (ref "F34") (pin "2") (pintype "passive"))
      (node (ref "Q102") (pin "2") (pinfunction "D_2") (pintype "passive"))
    )
    (net (code "44") (name "Net-(Q102-G)") (class "Default")
      (node (ref "C245") (pin "2") (pinfunction "2_2") (pintype "passive"))
      (node (ref "Q102") (pin "1") (pinfunction "G_1") (pintype "passive"))
      (node (ref "R367") (pin "2") (pinfunction "2_2") (pintype "passive"))
      (node (ref "R372") (pin "2") (pinfunction "2_2") (pintype "passive"))
    )
    (net (code "45") (name "Net-(Q103-D)") (class "Default")
      (node (ref "F35") (pin "2") (pintype "passive"))
      (node (ref "Q103") (pin "2") (pinfunction "D_2") (pintype "passive"))
    )
    (net (code "46") (name "Net-(Q103-G)") (class "Default")
      (node (ref "C246") (pin "2") (pinfunction "2_2") (pintype "passive"))
      (node (ref "Q103") (pin "1") (pinfunction "G_1") (pintype "passive"))
      (node (ref "R368") (pin "2") (pinfunction "2_2") (pintype "passive"))
      (node (ref "R373") (pin "2") (pinfunction "2_2") (pintype "passive"))
    )
    (net (code "47") (name "Net-(Q104-D)") (class "Default")
      (node (ref "F36") (pin "2") (pintype "passive"))
      (node (ref "Q104") (pin "2") (pinfunction "D_2") (pintype "passive"))
    )
    (net (code "48") (name "Net-(Q104-G)") (class "Default")
      (node (ref "C247") (pin "2") (pinfunction "2_2") (pintype "passive"))
      (node (ref "Q104") (pin "1") (pinfunction "G_1") (pintype "passive"))
      (node (ref "R369") (pin "2") (pinfunction "2_2") (pintype "passive"))
      (node (ref "R374") (pin "2") (pinfunction "2_2") (pintype "passive"))
    )
    (net (code "49") (name "Net-(Q105-D)") (class "Default")
      (node (ref "F37") (pin "2") (pintype "passive"))
      (node (ref "Q105") (pin "2") (pinfunction "D_2") (pintype "passive"))
    )
    (net (code "50") (name "Net-(Q105-G)") (class "Default")
      (node (ref "C248") (pin "2") (pinfunction "2_2") (pintype "passive"))
      (node (ref "Q105") (pin "1") (pinfunction "G_1") (pintype "passive"))
      (node (ref "R370") (pin "2") (pinfunction "2_2") (pintype "passive"))
      (node (ref "R375") (pin "2") (pinfunction "2_2") (pintype "passive"))
    )
    (net (code "51") (name "Net-(Q106-G)") (class "Default")
      (node (ref "D123") (pin "2") (pinfunction "2_2") (pintype "passive"))
      (node (ref "Q106") (pin "1") (pinfunction "G_1") (pintype "passive"))
      (node (ref "R381") (pin "1") (pinfunction "1_1") (pintype "passive"))
      (node (ref "R391") (pin "1") (pinfunction "1_1") (pintype "passive"))
    )
    (net (code "52") (name "Net-(Q107-G)") (class "Default")
      (node (ref "D124") (pin "2") (pinfunction "2_2") (pintype "passive"))
      (node (ref "Q107") (pin "1") (pinfunction "G_1") (pintype "passive"))
      (node (ref "R382") (pin "1") (pinfunction "1_1") (pintype "passive"))
      (node (ref "R392") (pin "1") (pinfunction "1_1") (pintype "passive"))
    )
    (net (code "53") (name "Net-(Q108-G)") (class "Default")
      (node (ref "D125") (pin "2") (pinfunction "2_2") (pintype "passive"))
      (node (ref "Q108") (pin "1") (pinfunction "G_1") (pintype "passive"))
      (node (ref "R383") (pin "1") (pinfunction "1_1") (pintype "passive"))
      (node (ref "R393") (pin "1") (pinfunction "1_1") (pintype "passive"))
    )
    (net (code "54") (name "Net-(Q109-G)") (class "Default")
      (node (ref "D126") (pin "2") (pinfunction "2_2") (pintype "passive"))
      (node (ref "Q109") (pin "1") (pinfunction "G_1") (pintype "passive"))
      (node (ref "R384") (pin "1") (pinfunction "1_1") (pintype "passive"))
      (node (ref "R394") (pin "1") (pinfunction "1_1") (pintype "passive"))
    )
    (net (code "55") (name "Net-(Q110-G)") (class "Default")
      (node (ref "D127") (pin "2") (pinfunction "2_2") (pintype "passive"))
      (node (ref "Q110") (pin "1") (pinfunction "G_1") (pintype "passive"))
      (node (ref "R385") (pin "1") (pinfunction "1_1") (pintype "passive"))
      (node (ref "R395") (pin "1") (pinfunction "1_1") (pintype "passive"))
    )
    (net (code "56") (name "Net-(Q111-D)") (class "Default")
      (node (ref "Q111") (pin "1") (pinfunction "D_1") (pintype "passive"))
      (node (ref "R391") (pin "2") (pinfunction "2_2") (pintype "passive"))
    )
    (net (code "57") (name "Net-(Q112-D)") (class "Default")
      (node (ref "Q112") (pin "1") (pinfunction "D_1") (pintype "passive"))
      (node (ref "R392") (pin "2") (pinfunction "2_2") (pintype "passive"))
    )
    (net (code "58") (name "Net-(Q113-D)") (class "Default")
      (node (ref "Q113") (pin "1") (pinfunction "D_1") (pintype "passive"))
      (node (ref "R393") (pin "2") (pinfunction "2_2") (pintype "passive"))
    )
    (net (code "59") (name "Net-(Q114-D)") (class "Default")
      (node (ref "Q114") (pin "1") (pinfunction "D_1") (pintype "passive"))
      (node (ref "R394") (pin "2") (pinfunction "2_2") (pintype "passive"))
    )
    (net (code "60") (name "Net-(Q115-D)") (class "Default")
      (node (ref "Q115") (pin "1") (pinfunction "D_1") (pintype "passive"))
      (node (ref "R395") (pin "2") (pinfunction "2_2") (pintype "passive"))
    )
    (net (code "61") (name "Net-(Q116-D)") (class "Default")
      (node (ref "F38") (pin "2") (pintype "passive"))
      (node (ref "Q116") (pin "2") (pinfunction "D_2") (pintype "passive"))
    )
    (net (code "62") (name "Net-(Q116-G)") (class "Default")
      (node (ref "C254") (pin "2") (pinfunction "2_2") (pintype "passive"))
      (node (ref "Q116") (pin "1") (pinfunction "G_1") (pintype "passive"))
      (node (ref "R401") (pin "2") (pinfunction "2_2") (pintype "passive"))
      (node (ref "R406") (pin "2") (pinfunction "2_2") (pintype "passive"))
    )
    (net (code "63") (name "Net-(Q117-D)") (class "Default")
      (node (ref "F39") (pin "2") (pintype "passive"))
      (node (ref "Q117") (pin "2") (pinfunction "D_2") (pintype "passive"))
    )
    (net (code "64") (name "Net-(Q117-G)") (class "Default")
      (node (ref "C255") (pin "2") (pinfunction "2_2") (pintype "passive"))
      (node (ref "Q117") (pin "1") (pinfunction "G_1") (pintype "passive"))
      (node (ref "R402") (pin "2") (pinfunction "2_2") (pintype "passive"))
      (node (ref "R407") (pin "2") (pinfunction "2_2") (pintype "passive"))
    )
    (net (code "65") (name "Net-(Q118-D)") (class "Default")
      (node (ref "F40") (pin "2") (pintype "passive"))
      (node (ref "Q118") (pin "2") (pinfunction "D_2") (pintype "passive"))
    )
    (net (code "66") (name "Net-(Q118-G)") (class "Default")
      (node (ref "C256") (pin "2") (pinfunction "2_2") (pintype "passive"))
      (node (ref "Q118") (pin "1") (pinfunction "G_1") (pintype "passive"))
      (node (ref "R403") (pin "2") (pinfunction "2_2") (pintype "passive"))
      (node (ref "R408") (pin "2") (pinfunction "2_2") (pintype "passive"))
    )
    (net (code "67") (name "Net-(Q119-D)") (class "Default")
      (node (ref "F41") (pin "2") (pintype "passive"))
      (node (ref "Q119") (pin "2") (pinfunction "D_2") (pintype "passive"))
    )
    (net (code "68") (name "Net-(Q119-G)") (class "Default")
      (node (ref "C257") (pin "2") (pinfunction "2_2") (pintype "passive"))
      (node (ref "Q119") (pin "1") (pinfunction "G_1") (pintype "passive"))
      (node (ref "R404") (pin "2") (pinfunction "2_2") (pintype "passive"))
      (node (ref "R409") (pin "2") (pinfunction "2_2") (pintype "passive"))
    )
    (net (code "69") (name "Net-(Q120-D)") (class "Default")
      (node (ref "F42") (pin "2") (pintype "passive"))
      (node (ref "Q120") (pin "2") (pinfunction "D_2") (pintype "passive"))
    )
    (net (code "70") (name "Net-(Q120-G)") (class "Default")
      (node (ref "C258") (pin "2") (pinfunction "2_2") (pintype "passive"))
      (node (ref "Q120") (pin "1") (pinfunction "G_1") (pintype "passive"))
      (node (ref "R405") (pin "2") (pinfunction "2_2") (pintype "passive"))
      (node (ref "R410") (pin "2") (pinfunction "2_2") (pintype "passive"))
    )
    (net (code "71") (name "Net-(Q121-G)") (class "Default")
      (node (ref "D133") (pin "2") (pinfunction "2_2") (pintype "passive"))
      (node (ref "Q121") (pin "1") (pinfunction "G_1") (pintype "passive"))
      (node (ref "R416") (pin "1") (pinfunction "1_1") (pintype "passive"))
      (node (ref "R426") (pin "1") (pinfunction "1_1") (pintype "passive"))
    )
    (net (code "72") (name "Net-(Q122-G)") (class "Default")
      (node (ref "D134") (pin "2") (pinfunction "2_2") (pintype "passive"))
      (node (ref "Q122") (pin "1") (pinfunction "G_1") (pintype "passive"))
      (node (ref "R417") (pin "1") (pinfunction "1_1") (pintype "passive"))
      (node (ref "R427") (pin "1") (pinfunction "1_1") (pintype "passive"))
    )
    (net (code "73") (name "Net-(Q123-G)") (class "Default")
      (node (ref "D135") (pin "2") (pinfunction "2_2") (pintype "passive"))
      (node (ref "Q123") (pin "1") (pinfunction "G_1") (pintype "passive"))
      (node (ref "R418") (pin "1") (pinfunction "1_1") (pintype "passive"))
      (node (ref "R428") (pin "1") (pinfunction "1_1") (pintype "passive"))
    )
    (net (code "74") (name "Net-(Q124-G)") (class "Default")
      (node (ref "D136") (pin "2") (pinfunction "2_2") (pintype "passive"))
      (node (ref "Q124") (pin "1") (pinfunction "G_1") (pintype "passive"))
      (node (ref "R419") (pin "1") (pinfunction "1_1") (pintype "passive"))
      (node (ref "R429") (pin "1") (pinfunction "1_1") (pintype "passive"))
    )
    (net (code "75") (name "Net-(Q125-G)") (class "Default")
      (node (ref "D137") (pin "2") (pinfunction "2_2") (pintype "passive"))
      (node (ref "Q125") (pin "1") (pinfunction "G_1") (pintype "passive"))
      (node (ref "R420") (pin "1") (pinfunction "1_1") (pintype "passive"))
      (node (ref "R430") (pin "1") (pinfunction "1_1") (pintype "passive"))
    )
    (net (code "76") (name "Net-(Q126-D)") (class "Default")
      (node (ref "Q126") (pin "1") (pinfunction "D_1") (pintype "passive"))
      (node (ref "R426") (pin "2") (pinfunction "2_2") (pintype "passive"))
    )
    (net (code "77") (name "Net-(Q127-D)") (class "Default")
      (node (ref "Q127") (pin "1") (pinfunction "D_1") (pintype "passive"))
      (node (ref "R427") (pin "2") (pinfunction "2_2") (pintype "passive"))
    )
    (net (code "78") (name "Net-(Q128-D)") (class "Default")
      (node (ref "Q128") (pin "1") (pinfunction "D_1") (pintype "passive"))
      (node (ref "R428") (pin "2") (pinfunction "2_2") (pintype "passive"))
    )
    (net (code "79") (name "Net-(Q129-D)") (class "Default")
      (node (ref "Q129") (pin "1") (pinfunction "D_1") (pintype "passive"))
      (node (ref "R429") (pin "2") (pinfunction "2_2") (pintype "passive"))
    )
    (net (code "80") (name "Net-(Q130-D)") (class "Default")
      (node (ref "Q130") (pin "1") (pinfunction "D_1") (pintype "passive"))
      (node (ref "R430") (pin "2") (pinfunction "2_2") (pintype "passive"))
    )
    (net (code "81") (name "Net-(Q131-D)") (class "Default")
      (node (ref "F43") (pin "2") (pintype "passive"))
      (node (ref "Q131") (pin "2") (pinfunction "D_2") (pintype "passive"))
    )
    (net (code "82") (name "Net-(Q131-G)") (class "Default")
      (node (ref "C264") (pin "2") (pinfunction "2_2") (pintype "passive"))
      (node (ref "Q131") (pin "1") (pinfunction "G_1") (pintype "passive"))
      (node (ref "R436") (pin "2") (pinfunction "2_2") (pintype "passive"))
      (node (ref "R441") (pin "2") (pinfunction "2_2") (pintype "passive"))
    )
    (net (code "83") (name "Net-(Q132-D)") (class "Default")
      (node (ref "F44") (pin "2") (pintype "passive"))
      (node (ref "Q132") (pin "2") (pinfunction "D_2") (pintype "passive"))
    )
    (net (code "84") (name "Net-(Q132-G)") (class "Default")
      (node (ref "C265") (pin "2") (pinfunction "2_2") (pintype "passive"))
      (node (ref "Q132") (pin "1") (pinfunction "G_1") (pintype "passive"))
      (node (ref "R437") (pin "2") (pinfunction "2_2") (pintype "passive"))
      (node (ref "R442") (pin "2") (pinfunction "2_2") (pintype "passive"))
    )
    (net (code "85") (name "Net-(Q133-D)") (class "Default")
      (node (ref "F45") (pin "2") (pintype "passive"))
      (node (ref "Q133") (pin "2") (pinfunction "D_2") (pintype "passive"))
    )
    (net (code "86") (name "Net-(Q133-G)") (class "Default")
      (node (ref "C266") (pin "2") (pinfunction "2_2") (pintype "passive"))
      (node (ref "Q133") (pin "1") (pinfunction "G_1") (pintype "passive"))
      (node (ref "R438") (pin "2") (pinfunction "2_2") (pintype "passive"))
      (node (ref "R443") (pin "2") (pinfunction "2_2") (pintype "passive"))
    )
    (net (code "87") (name "Net-(Q134-D)") (class "Default")
      (node (ref "F46") (pin "2") (pintype "passive"))
      (node (ref "Q134") (pin "2") (pinfunction "D_2") (pintype "passive"))
    )
    (net (code "88") (name "Net-(Q134-G)") (class "Default")
      (node (ref "C267") (pin "2") (pinfunction "2_2") (pintype "passive"))
      (node (ref "Q134") (pin "1") (pinfunction "G_1") (pintype "passive"))
      (node (ref "R439") (pin "2") (pinfunction "2_2") (pintype "passive"))
      (node (ref "R444") (pin "2") (pinfunction "2_2") (pintype "passive"))
    )
    (net (code "89") (name "Net-(Q135-D)") (class "Default")
      (node (ref "F47") (pin "2") (pintype "passive"))
      (node (ref "Q135") (pin "2") (pinfunction "D_2") (pintype "passive"))
    )
    (net (code "90") (name "Net-(Q135-G)") (class "Default")
      (node (ref "C268") (pin "2") (pinfunction "2_2") (pintype "passive"))
      (node (ref "Q135") (pin "1") (pinfunction "G_1") (pintype "passive"))
      (node (ref "R440") (pin "2") (pinfunction "2_2") (pintype "passive"))
      (node (ref "R445") (pin "2") (pinfunction "2_2") (pintype "passive"))
    )
    (net (code "91") (name "PF31+") (class "Default")
      (node (ref "C239") (pin "2") (pinfunction "2_2") (pintype "passive"))
      (node (ref "Q96") (pin "2") (pinfunction "G_2") (pintype "passive"))
      (node (ref "R361") (pin "2") (pinfunction "2_2") (pintype "passive"))
    )
    (net (code "92") (name "PF31-") (class "Default")
      (node (ref "R366") (pin "1") (pinfunction "1_1") (pintype "passive"))
      (node (ref "R376") (pin "1") (pinfunction "1_1") (pintype "passive"))
    )
    (net (code "93") (name "PF32+") (class "Default")
      (node (ref "C240") (pin "2") (pinfunction "2_2") (pintype "passive"))
      (node (ref "Q97") (pin "2") (pinfunction "G_2") (pintype "passive"))
      (node (ref "R362") (pin "2") (pinfunction "2_2") (pintype "passive"))
    )
    (net (code "94") (name "PF32-") (class "Default")
      (node (ref "R367") (pin "1") (pinfunction "1_1") (pintype "passive"))
      (node (ref "R377") (pin "1") (pinfunction "1_1") (pintype "passive"))
    )
    (net (code "95") (name "PF33+") (class "Default")
      (node (ref "C241") (pin "2") (pinfunction "2_2") (pintype "passive"))
      (node (ref "Q98") (pin "2") (pinfunction "G_2") (pintype "passive"))
      (node (ref "R363") (pin "2") (pinfunction "2_2") (pintype "passive"))
    )
    (net (code "96") (name "PF33-") (class "Default")
      (node (ref "R368") (pin "1") (pinfunction "1_1") (pintype "passive"))
      (node (ref "R378") (pin "1") (pinfunction "1_1") (pintype "passive"))
    )
    (net (code "97") (name "PF34+") (class "Default")
      (node (ref "C242") (pin "2") (pinfunction "2_2") (pintype "passive"))
      (node (ref "Q99") (pin "2") (pinfunction "G_2") (pintype "passive"))
      (node (ref "R364") (pin "2") (pinfunction "2_2") (pintype "passive"))
    )
    (net (code "98") (name "PF34-") (class "Default")
      (node (ref "R369") (pin "1") (pinfunction "1_1") (pintype "passive"))
      (node (ref "R379") (pin "1") (pinfunction "1_1") (pintype "passive"))
    )
    (net (code "99") (name "PF35+") (class "Default")
      (node (ref "C243") (pin "2") (pinfunction "2_2") (pintype "passive"))
      (node (ref "Q100") (pin "2") (pinfunction "G_2") (pintype "passive"))
      (node (ref "R365") (pin "2") (pinfunction "2_2") (pintype "passive"))
    )
    (net (code "100") (name "PF35-") (class "Default")
      (node (ref "R370") (pin "1") (pinfunction "1_1") (pintype "passive"))
      (node (ref "R380") (pin "1") (pinfunction "1_1") (pintype "passive"))
    )
    (net (code "101") (name "PF36+") (class "Default")
      (node (ref "C249") (pin "2") (pinfunction "2_2") (pintype "passive"))
      (node (ref "Q111") (pin "2") (pinfunction "G_2") (pintype "passive"))
      (node (ref "R396") (pin "2") (pinfunction "2_2") (pintype "passive"))
    )
    (net (code "102") (name "PF36-") (class "Default")
      (node (ref "R401") (pin "1") (pinfunction "1_1") (pintype "passive"))
      (node (ref "R411") (pin "1") (pinfunction "1_1") (pintype "passive"))
    )
    (net (code "103") (name "PF37+") (class "Default")
      (node (ref "C250") (pin "2") (pinfunction "2_2") (pintype "passive"))
      (node (ref "Q112") (pin "2") (pinfunction "G_2") (pintype "passive"))
      (node (ref "R397") (pin "2") (pinfunction "2_2") (pintype "passive"))
    )
    (net (code "104") (name "PF37-") (class "Default")
      (node (ref "R402") (pin "1") (pinfunction "1_1") (pintype "passive"))
      (node (ref "R412") (pin "1") (pinfunction "1_1") (pintype "passive"))
    )
    (net (code "105") (name "PF38+") (class "Default")
      (node (ref "C251") (pin "2") (pinfunction "2_2") (pintype "passive"))
      (node (ref "Q113") (pin "2") (pinfunction "G_2") (pintype "passive"))
      (node (ref "R398") (pin "2") (pinfunction "2_2") (pintype "passive"))
    )
    (net (code "106") (name "PF38-") (class "Default")
      (node (ref "R403") (pin "1") (pinfunction "1_1") (pintype "passive"))
      (node (ref "R413") (pin "1") (pinfunction "1_1") (pintype "passive"))
    )
    (net (code "107") (name "PF39+") (class "Default")
      (node (ref "C252") (pin "2") (pinfunction "2_2") (pintype "passive"))
      (node (ref "Q114") (pin "2") (pinfunction "G_2") (pintype "passive"))
      (node (ref "R399") (pin "2") (pinfunction "2_2") (pintype "passive"))
    )
    (net (code "108") (name "PF39-") (class "Default")
      (node (ref "R404") (pin "1") (pinfunction "1_1") (pintype "passive"))
      (node (ref "R414") (pin "1") (pinfunction "1_1") (pintype "passive"))
    )
    (net (code "109") (name "PF40+") (class "Default")
      (node (ref "C253") (pin "2") (pinfunction "2_2") (pintype "passive"))
      (node (ref "Q115") (pin "2") (pinfunction "G_2") (pintype "passive"))
      (node (ref "R400") (pin "2") (pinfunction "2_2") (pintype "passive"))
    )
    (net (code "110") (name "PF40-") (class "Default")
      (node (ref "R405") (pin "1") (pinfunction "1_1") (pintype "passive"))
      (node (ref "R415") (pin "1") (pinfunction "1_1") (pintype "passive"))
    )
    (net (code "111") (name "PF41+") (class "Default")
      (node (ref "C259") (pin "2") (pinfunction "2_2") (pintype "passive"))
      (node (ref "Q126") (pin "2") (pinfunction "G_2") (pintype "passive"))
      (node (ref "R431") (pin "2") (pinfunction "2_2") (pintype "passive"))
    )
    (net (code "112") (name "PF41-") (class "Default")
      (node (ref "R436") (pin "1") (pinfunction "1_1") (pintype "passive"))
      (node (ref "R446") (pin "1") (pinfunction "1_1") (pintype "passive"))
    )
    (net (code "113") (name "PF42+") (class "Default")
      (node (ref "C260") (pin "2") (pinfunction "2_2") (pintype "passive"))
      (node (ref "Q127") (pin "2") (pinfunction "G_2") (pintype "passive"))
      (node (ref "R432") (pin "2") (pinfunction "2_2") (pintype "passive"))
    )
    (net (code "114") (name "PF42-") (class "Default")
      (node (ref "R437") (pin "1") (pinfunction "1_1") (pintype "passive"))
      (node (ref "R447") (pin "1") (pinfunction "1_1") (pintype "passive"))
    )
    (net (code "115") (name "PF43+") (class "Default")
      (node (ref "C261") (pin "2") (pinfunction "2_2") (pintype "passive"))
      (node (ref "Q128") (pin "2") (pinfunction "G_2") (pintype "passive"))
      (node (ref "R433") (pin "2") (pinfunction "2_2") (pintype "passive"))
    )
    (net (code "116") (name "PF43-") (class "Default")
      (node (ref "R438") (pin "1") (pinfunction "1_1") (pintype "passive"))
      (node (ref "R448") (pin "1") (pinfunction "1_1") (pintype "passive"))
    )
    (net (code "117") (name "PF44+") (class "Default")
      (node (ref "C262") (pin "2") (pinfunction "2_2") (pintype "passive"))
      (node (ref "Q129") (pin "2") (pinfunction "G_2") (pintype "passive"))
      (node (ref "R434") (pin "2") (pinfunction "2_2") (pintype "passive"))
    )
    (net (code "118") (name "PF44-") (class "Default")
      (node (ref "R439") (pin "1") (pinfunction "1_1") (pintype "passive"))
      (node (ref "R449") (pin "1") (pinfunction "1_1") (pintype "passive"))
    )
    (net (code "119") (name "PF45+") (class "Default")
      (node (ref "C263") (pin "2") (pinfunction "2_2") (pintype "passive"))
      (node (ref "Q130") (pin "2") (pinfunction "G_2") (pintype "passive"))
      (node (ref "R435") (pin "2") (pinfunction "2_2") (pintype "passive"))
    )
    (net (code "120") (name "PF45-") (class "Default")
      (node (ref "R440") (pin "1") (pinfunction "1_1") (pintype "passive"))
      (node (ref "R450") (pin "1") (pinfunction "1_1") (pintype "passive"))
    )
    (net (code "121") (name "PGND") (class "Default")
      (node (ref "C239") (pin "1") (pinfunction "1_1") (pintype "passive"))
      (node (ref "C240") (pin "1") (pinfunction "1_1") (pintype "passive"))
      (node (ref "C241") (pin "1") (pinfunction "1_1") (pintype "passive"))
      (node (ref "C242") (pin "1") (pinfunction "1_1") (pintype "passive"))
      (node (ref "C243") (pin "1") (pinfunction "1_1") (pintype "passive"))
      (node (ref "C244") (pin "1") (pinfunction "1_1") (pintype "passive"))
      (node (ref "C245") (pin "1") (pinfunction "1_1") (pintype "passive"))
      (node (ref "C246") (pin "1") (pinfunction "1_1") (pintype "passive"))
      (node (ref "C247") (pin "1") (pinfunction "1_1") (pintype "passive"))
      (node (ref "C248") (pin "1") (pinfunction "1_1") (pintype "passive"))
      (node (ref "C249") (pin "1") (pinfunction "1_1") (pintype "passive"))
      (node (ref "C250") (pin "1") (pinfunction "1_1") (pintype "passive"))
      (node (ref "C251") (pin "1") (pinfunction "1_1") (pintype "passive"))
      (node (ref "C252") (pin "1") (pinfunction "1_1") (pintype "passive"))
      (node (ref "C253") (pin "1") (pinfunction "1_1") (pintype "passive"))
      (node (ref "C254") (pin "1") (pinfunction "1_1") (pintype "passive"))
      (node (ref "C255") (pin "1") (pinfunction "1_1") (pintype "passive"))
      (node (ref "C256") (pin "1") (pinfunction "1_1") (pintype "passive"))
      (node (ref "C257") (pin "1") (pinfunction "1_1") (pintype "passive"))
      (node (ref "C258") (pin "1") (pinfunction "1_1") (pintype "passive"))
      (node (ref "C259") (pin "1") (pinfunction "1_1") (pintype "passive"))
      (node (ref "C260") (pin "1") (pinfunction "1_1") (pintype "passive"))
      (node (ref "C261") (pin "1") (pinfunction "1_1") (pintype "passive"))
      (node (ref "C262") (pin "1") (pinfunction "1_1") (pintype "passive"))
      (node (ref "C263") (pin "1") (pinfunction "1_1") (pintype "passive"))
      (node (ref "C264") (pin "1") (pinfunction "1_1") (pintype "passive"))
      (node (ref "C265") (pin "1") (pinfunction "1_1") (pintype "passive"))
      (node (ref "C266") (pin "1") (pinfunction "1_1") (pintype "passive"))
      (node (ref "C267") (pin "1") (pinfunction "1_1") (pintype "passive"))
      (node (ref "C268") (pin "1") (pinfunction "1_1") (pintype "passive"))
      (node (ref "Q100") (pin "3") (pinfunction "S_3") (pintype "passive"))
      (node (ref "Q101") (pin "3") (pinfunction "S_3") (pintype "passive"))
      (node (ref "Q102") (pin "3") (pinfunction "S_3") (pintype "passive"))
      (node (ref "Q103") (pin "3") (pinfunction "S_3") (pintype "passive"))
      (node (ref "Q104") (pin "3") (pinfunction "S_3") (pintype "passive"))
      (node (ref "Q105") (pin "3") (pinfunction "S_3") (pintype "passive"))
      (node (ref "Q111") (pin "3") (pinfunction "S_3") (pintype "passive"))
      (node (ref "Q112") (pin "3") (pinfunction "S_3") (pintype "passive"))
      (node (ref "Q113") (pin "3") (pinfunction "S_3") (pintype "passive"))
      (node (ref "Q114") (pin "3") (pinfunction "S_3") (pintype "passive"))
      (node (ref "Q115") (pin "3") (pinfunction "S_3") (pintype "passive"))
      (node (ref "Q116") (pin "3") (pinfunction "S_3") (pintype "passive"))
      (node (ref "Q117") (pin "3") (pinfunction "S_3") (pintype "passive"))
      (node (ref "Q118") (pin "3") (pinfunction "S_3") (pintype "passive"))
      (node (ref "Q119") (pin "3") (pinfunction "S_3") (pintype "passive"))
      (node (ref "Q120") (pin "3") (pinfunction "S_3") (pintype "passive"))
      (node (ref "Q126") (pin "3") (pinfunction "S_3") (pintype "passive"))
      (node (ref "Q127") (pin "3") (pinfunction "S_3") (pintype "passive"))
      (node (ref "Q128") (pin "3") (pinfunction "S_3") (pintype "passive"))
      (node (ref "Q129") (pin "3") (pinfunction "S_3") (pintype "passive"))
      (node (ref "Q130") (pin "3") (pinfunction "S_3") (pintype "passive"))
      (node (ref "Q131") (pin "3") (pinfunction "S_3") (pintype "passive"))
      (node (ref "Q132") (pin "3") (pinfunction "S_3") (pintype "passive"))
      (node (ref "Q133") (pin "3") (pinfunction "S_3") (pintype "passive"))
      (node (ref "Q134") (pin "3") (pinfunction "S_3") (pintype "passive"))
      (node (ref "Q135") (pin "3") (pinfunction "S_3") (pintype "passive"))
      (node (ref "Q96") (pin "3") (pinfunction "S_3") (pintype "passive"))
      (node (ref "Q97") (pin "3") (pinfunction "S_3") (pintype "passive"))
      (node (ref "Q98") (pin "3") (pinfunction "S_3") (pintype "passive"))
      (node (ref "Q99") (pin "3") (pinfunction "S_3") (pintype "passive"))
      (node (ref "R361") (pin "1") (pinfunction "1_1") (pintype "passive"))
      (node (ref "R362") (pin "1") (pinfunction "1_1") (pintype "passive"))
      (node (ref "R363") (pin "1") (pinfunction "1_1") (pintype "passive"))
      (node (ref "R364") (pin "1") (pinfunction "1_1") (pintype "passive"))
      (node (ref "R365") (pin "1") (pinfunction "1_1") (pintype "passive"))
      (node (ref "R371") (pin "1") (pinfunction "1_1") (pintype "passive"))
      (node (ref "R372") (pin "1") (pinfunction "1_1") (pintype "passive"))
      (node (ref "R373") (pin "1") (pinfunction "1_1") (pintype "passive"))
      (node (ref "R374") (pin "1") (pinfunction "1_1") (pintype "passive"))
      (node (ref "R375") (pin "1") (pinfunction "1_1") (pintype "passive"))
      (node (ref "R376") (pin "2") (pinfunction "2_2") (pintype "passive"))
      (node (ref "R377") (pin "2") (pinfunction "2_2") (pintype "passive"))
      (node (ref "R378") (pin "2") (pinfunction "2_2") (pintype "passive"))
      (node (ref "R379") (pin "2") (pinfunction "2_2") (pintype "passive"))
      (node (ref "R380") (pin "2") (pinfunction "2_2") (pintype "passive"))
      (node (ref "R396") (pin "1") (pinfunction "1_1") (pintype "passive"))
      (node (ref "R397") (pin "1") (pinfunction "1_1") (pintype "passive"))
      (node (ref "R398") (pin "1") (pinfunction "1_1") (pintype "passive"))
      (node (ref "R399") (pin "1") (pinfunction "1_1") (pintype "passive"))
      (node (ref "R400") (pin "1") (pinfunction "1_1") (pintype "passive"))
      (node (ref "R406") (pin "1") (pinfunction "1_1") (pintype "passive"))
      (node (ref "R407") (pin "1") (pinfunction "1_1") (pintype "passive"))
      (node (ref "R408") (pin "1") (pinfunction "1_1") (pintype "passive"))
      (node (ref "R409") (pin "1") (pinfunction "1_1") (pintype "passive"))
      (node (ref "R410") (pin "1") (pinfunction "1_1") (pintype "passive"))
      (node (ref "R411") (pin "2") (pinfunction "2_2") (pintype "passive"))
      (node (ref "R412") (pin "2") (pinfunction "2_2") (pintype "passive"))
      (node (ref "R413") (pin "2") (pinfunction "2_2") (pintype "passive"))
      (node (ref "R414") (pin "2") (pinfunction "2_2") (pintype "passive"))
      (node (ref "R415") (pin "2") (pinfunction "2_2") (pintype "passive"))
      (node (ref "R431") (pin "1") (pinfunction "1_1") (pintype "passive"))
      (node (ref "R432") (pin "1") (pinfunction "1_1") (pintype "passive"))
      (node (ref "R433") (pin "1") (pinfunction "1_1") (pintype "passive"))
      (node (ref "R434") (pin "1") (pinfunction "1_1") (pintype "passive"))
      (node (ref "R435") (pin "1") (pinfunction "1_1") (pintype "passive"))
      (node (ref "R441") (pin "1") (pinfunction "1_1") (pintype "passive"))
      (node (ref "R442") (pin "1") (pinfunction "1_1") (pintype "passive"))
      (node (ref "R443") (pin "1") (pinfunction "1_1") (pintype "passive"))
      (node (ref "R444") (pin "1") (pinfunction "1_1") (pintype "passive"))
      (node (ref "R445") (pin "1") (pinfunction "1_1") (pintype "passive"))
      (node (ref "R446") (pin "2") (pinfunction "2_2") (pintype "passive"))
      (node (ref "R447") (pin "2") (pinfunction "2_2") (pintype "passive"))
      (node (ref "R448") (pin "2") (pinfunction "2_2") (pintype "passive"))
      (node (ref "R449") (pin "2") (pinfunction "2_2") (pintype "passive"))
      (node (ref "R450") (pin "2") (pinfunction "2_2") (pintype "passive"))
    )
    (net (code "122") (name "PHIGH") (class "Default")
      (node (ref "D113") (pin "1") (pinfunction "1_1") (pintype "passive"))
      (node (ref "D114") (pin "1") (pinfunction "1_1") (pintype "passive"))
      (node (ref "D115") (pin "1") (pinfunction "1_1") (pintype "passive"))
      (node (ref "D116") (pin "1") (pinfunction "1_1") (pintype "passive"))
      (node (ref "D117") (pin "1") (pinfunction "1_1") (pintype "passive"))
      (node (ref "D123") (pin "1") (pinfunction "1_1") (pintype "passive"))
      (node (ref "D124") (pin "1") (pinfunction "1_1") (pintype "passive"))
      (node (ref "D125") (pin "1") (pinfunction "1_1") (pintype "passive"))
      (node (ref "D126") (pin "1") (pinfunction "1_1") (pintype "passive"))
      (node (ref "D127") (pin "1") (pinfunction "1_1") (pintype "passive"))
      (node (ref "D133") (pin "1") (pinfunction "1_1") (pintype "passive"))
      (node (ref "D134") (pin "1") (pinfunction "1_1") (pintype "passive"))
      (node (ref "D135") (pin "1") (pinfunction "1_1") (pintype "passive"))
      (node (ref "D136") (pin "1") (pinfunction "1_1") (pintype "passive"))
      (node (ref "D137") (pin "1") (pinfunction "1_1") (pintype "passive"))
      (node (ref "Q106") (pin "3") (pinfunction "S_3") (pintype "passive"))
      (node (ref "Q107") (pin "3") (pinfunction "S_3") (pintype "passive"))
      (node (ref "Q108") (pin "3") (pinfunction "S_3") (pintype "passive"))
      (node (ref "Q109") (pin "3") (pinfunction "S_3") (pintype "passive"))
      (node (ref "Q110") (pin "3") (pinfunction "S_3") (pintype "passive"))
      (node (ref "Q121") (pin "3") (pinfunction "S_3") (pintype "passive"))
      (node (ref "Q122") (pin "3") (pinfunction "S_3") (pintype "passive"))
      (node (ref "Q123") (pin "3") (pinfunction "S_3") (pintype "passive"))
      (node (ref "Q124") (pin "3") (pinfunction "S_3") (pintype "passive"))
      (node (ref "Q125") (pin "3") (pinfunction "S_3") (pintype "passive"))
      (node (ref "Q91") (pin "3") (pinfunction "S_3") (pintype "passive"))
      (node (ref "Q92") (pin "3") (pinfunction "S_3") (pintype "passive"))
      (node (ref "Q93") (pin "3") (pinfunction "S_3") (pintype "passive"))
      (node (ref "Q94") (pin "3") (pinfunction "S_3") (pintype "passive"))
      (node (ref "Q95") (pin "3") (pinfunction "S_3") (pintype "passive"))
      (node (ref "R346") (pin "2") (pinfunction "2_2") (pintype "passive"))
      (node (ref "R347") (pin "2") (pinfunction "2_2") (pintype "passive"))
      (node (ref "R348") (pin "2") (pinfunction "2_2") (pintype "passive"))
      (node (ref "R349") (pin "2") (pinfunction "2_2") (pintype "passive"))
      (node (ref "R350") (pin "2") (pinfunction "2_2") (pintype "passive"))
      (node (ref "R351") (pin "2") (pinfunction "2_2") (pintype "passive"))
      (node (ref "R352") (pin "2") (pinfunction "2_2") (pintype "passive"))
      (node (ref "R353") (pin "2") (pinfunction "2_2") (pintype "passive"))
      (node (ref "R354") (pin "2") (pinfunction "2_2") (pintype "passive"))
      (node (ref "R355") (pin "2") (pinfunction "2_2") (pintype "passive"))
      (node (ref "R381") (pin "2") (pinfunction "2_2") (pintype "passive"))
      (node (ref "R382") (pin "2") (pinfunction "2_2") (pintype "passive"))
      (node (ref "R383") (pin "2") (pinfunction "2_2") (pintype "passive"))
      (node (ref "R384") (pin "2") (pinfunction "2_2") (pintype "passive"))
      (node (ref "R385") (pin "2") (pinfunction "2_2") (pintype "passive"))
      (node (ref "R386") (pin "2") (pinfunction "2_2") (pintype "passive"))
      (node (ref "R387") (pin "2") (pinfunction "2_2") (pintype "passive"))
      (node (ref "R388") (pin "2") (pinfunction "2_2") (pintype "passive"))
      (node (ref "R389") (pin "2") (pinfunction "2_2") (pintype "passive"))
      (node (ref "R390") (pin "2") (pinfunction "2_2") (pintype "passive"))
      (node (ref "R416") (pin "2") (pinfunction "2_2") (pintype "passive"))
      (node (ref "R417") (pin "2") (pinfunction "2_2") (pintype "passive"))
      (node (ref "R418") (pin "2") (pinfunction "2_2") (pintype "passive"))
      (node (ref "R419") (pin "2") (pinfunction "2_2") (pintype "passive"))
      (node (ref "R420") (pin "2") (pinfunction "2_2") (pintype "passive"))
      (node (ref "R421") (pin "2") (pinfunction "2_2") (pintype "passive"))
      (node (ref "R422") (pin "2") (pinfunction "2_2") (pintype "passive"))
      (node (ref "R423") (pin "2") (pinfunction "2_2") (pintype "passive"))
      (node (ref "R424") (pin "2") (pinfunction "2_2") (pintype "passive"))
      (node (ref "R425") (pin "2") (pinfunction "2_2") (pintype "passive"))
    )
    (net (code "123") (name "PLOW") (class "Default")
      (node (ref "D118") (pin "2") (pinfunction "2_2") (pintype "passive"))
      (node (ref "D119") (pin "2") (pinfunction "2_2") (pintype "passive"))
      (node (ref "D120") (pin "2") (pinfunction "2_2") (pintype "passive"))
      (node (ref "D121") (pin "2") (pinfunction "2_2") (pintype "passive"))
      (node (ref "D122") (pin "2") (pinfunction "2_2") (pintype "passive"))
      (node (ref "D128") (pin "2") (pinfunction "2_2") (pintype "passive"))
      (node (ref "D129") (pin "2") (pinfunction "2_2") (pintype "passive"))
      (node (ref "D130") (pin "2") (pinfunction "2_2") (pintype "passive"))
      (node (ref "D131") (pin "2") (pinfunction "2_2") (pintype "passive"))
      (node (ref "D132") (pin "2") (pinfunction "2_2") (pintype "passive"))
      (node (ref "D138") (pin "2") (pinfunction "2_2") (pintype "passive"))
      (node (ref "D139") (pin "2") (pinfunction "2_2") (pintype "passive"))
      (node (ref "D140") (pin "2") (pinfunction "2_2") (pintype "passive"))
      (node (ref "D141") (pin "2") (pinfunction "2_2") (pintype "passive"))
      (node (ref "D142") (pin "2") (pinfunction "2_2") (pintype "passive"))
    )
  )
)
